# actuator_control_1_2_0.net
KiCad netlist of a schematic drawn in EAGLE
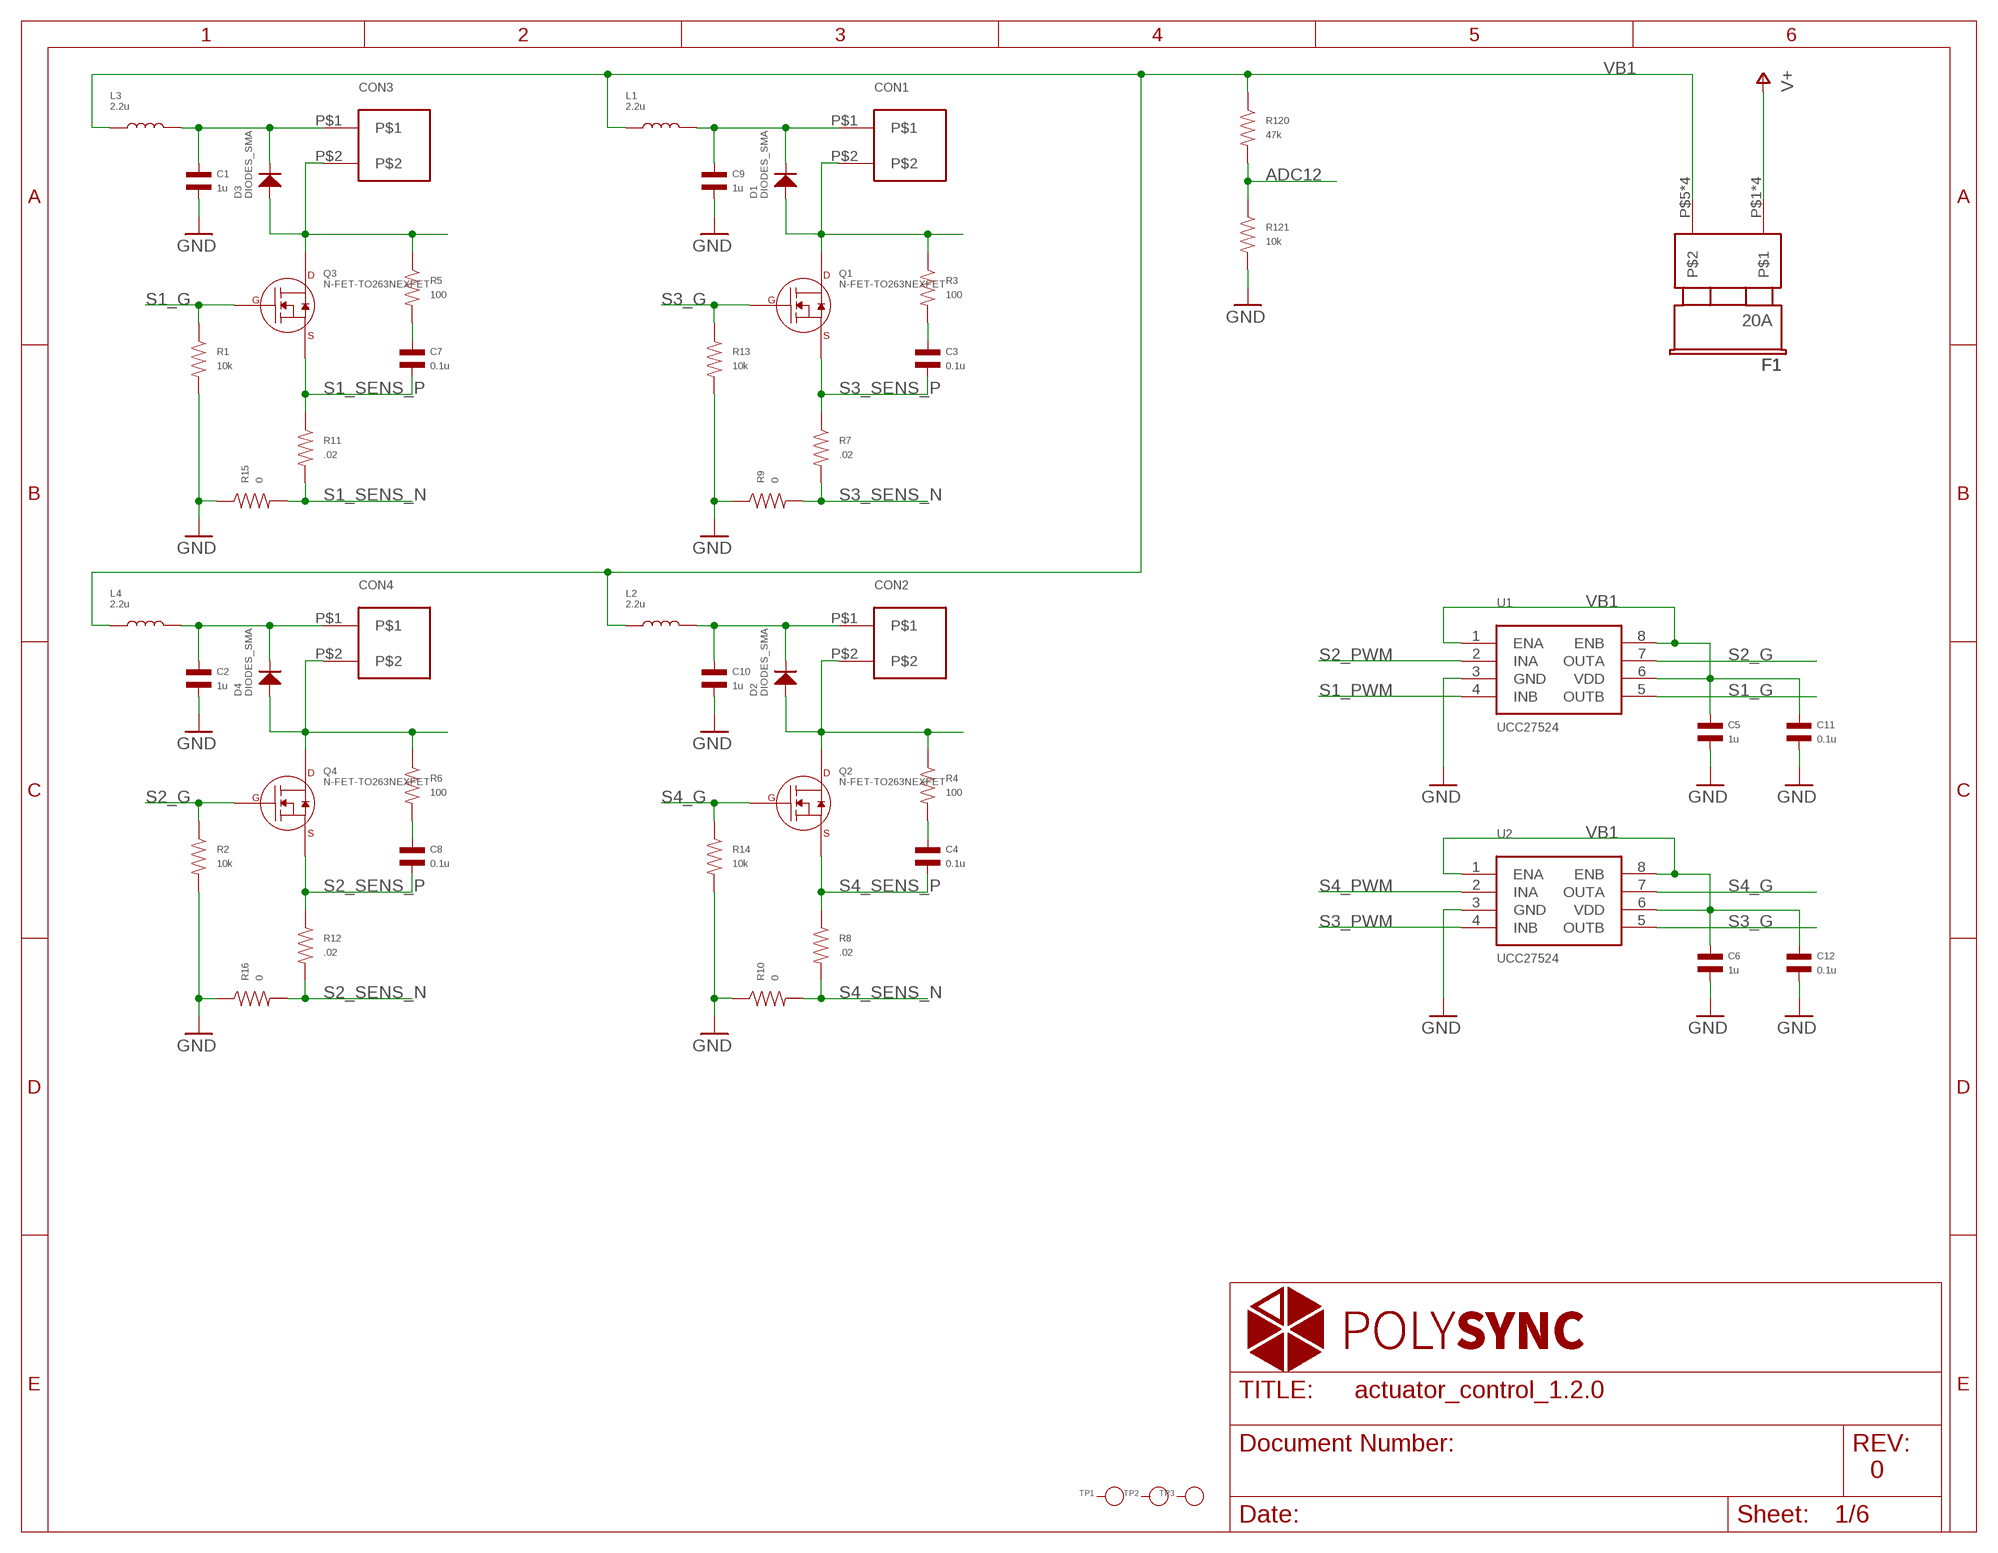
[diagram p0: schematic, sheet 1]
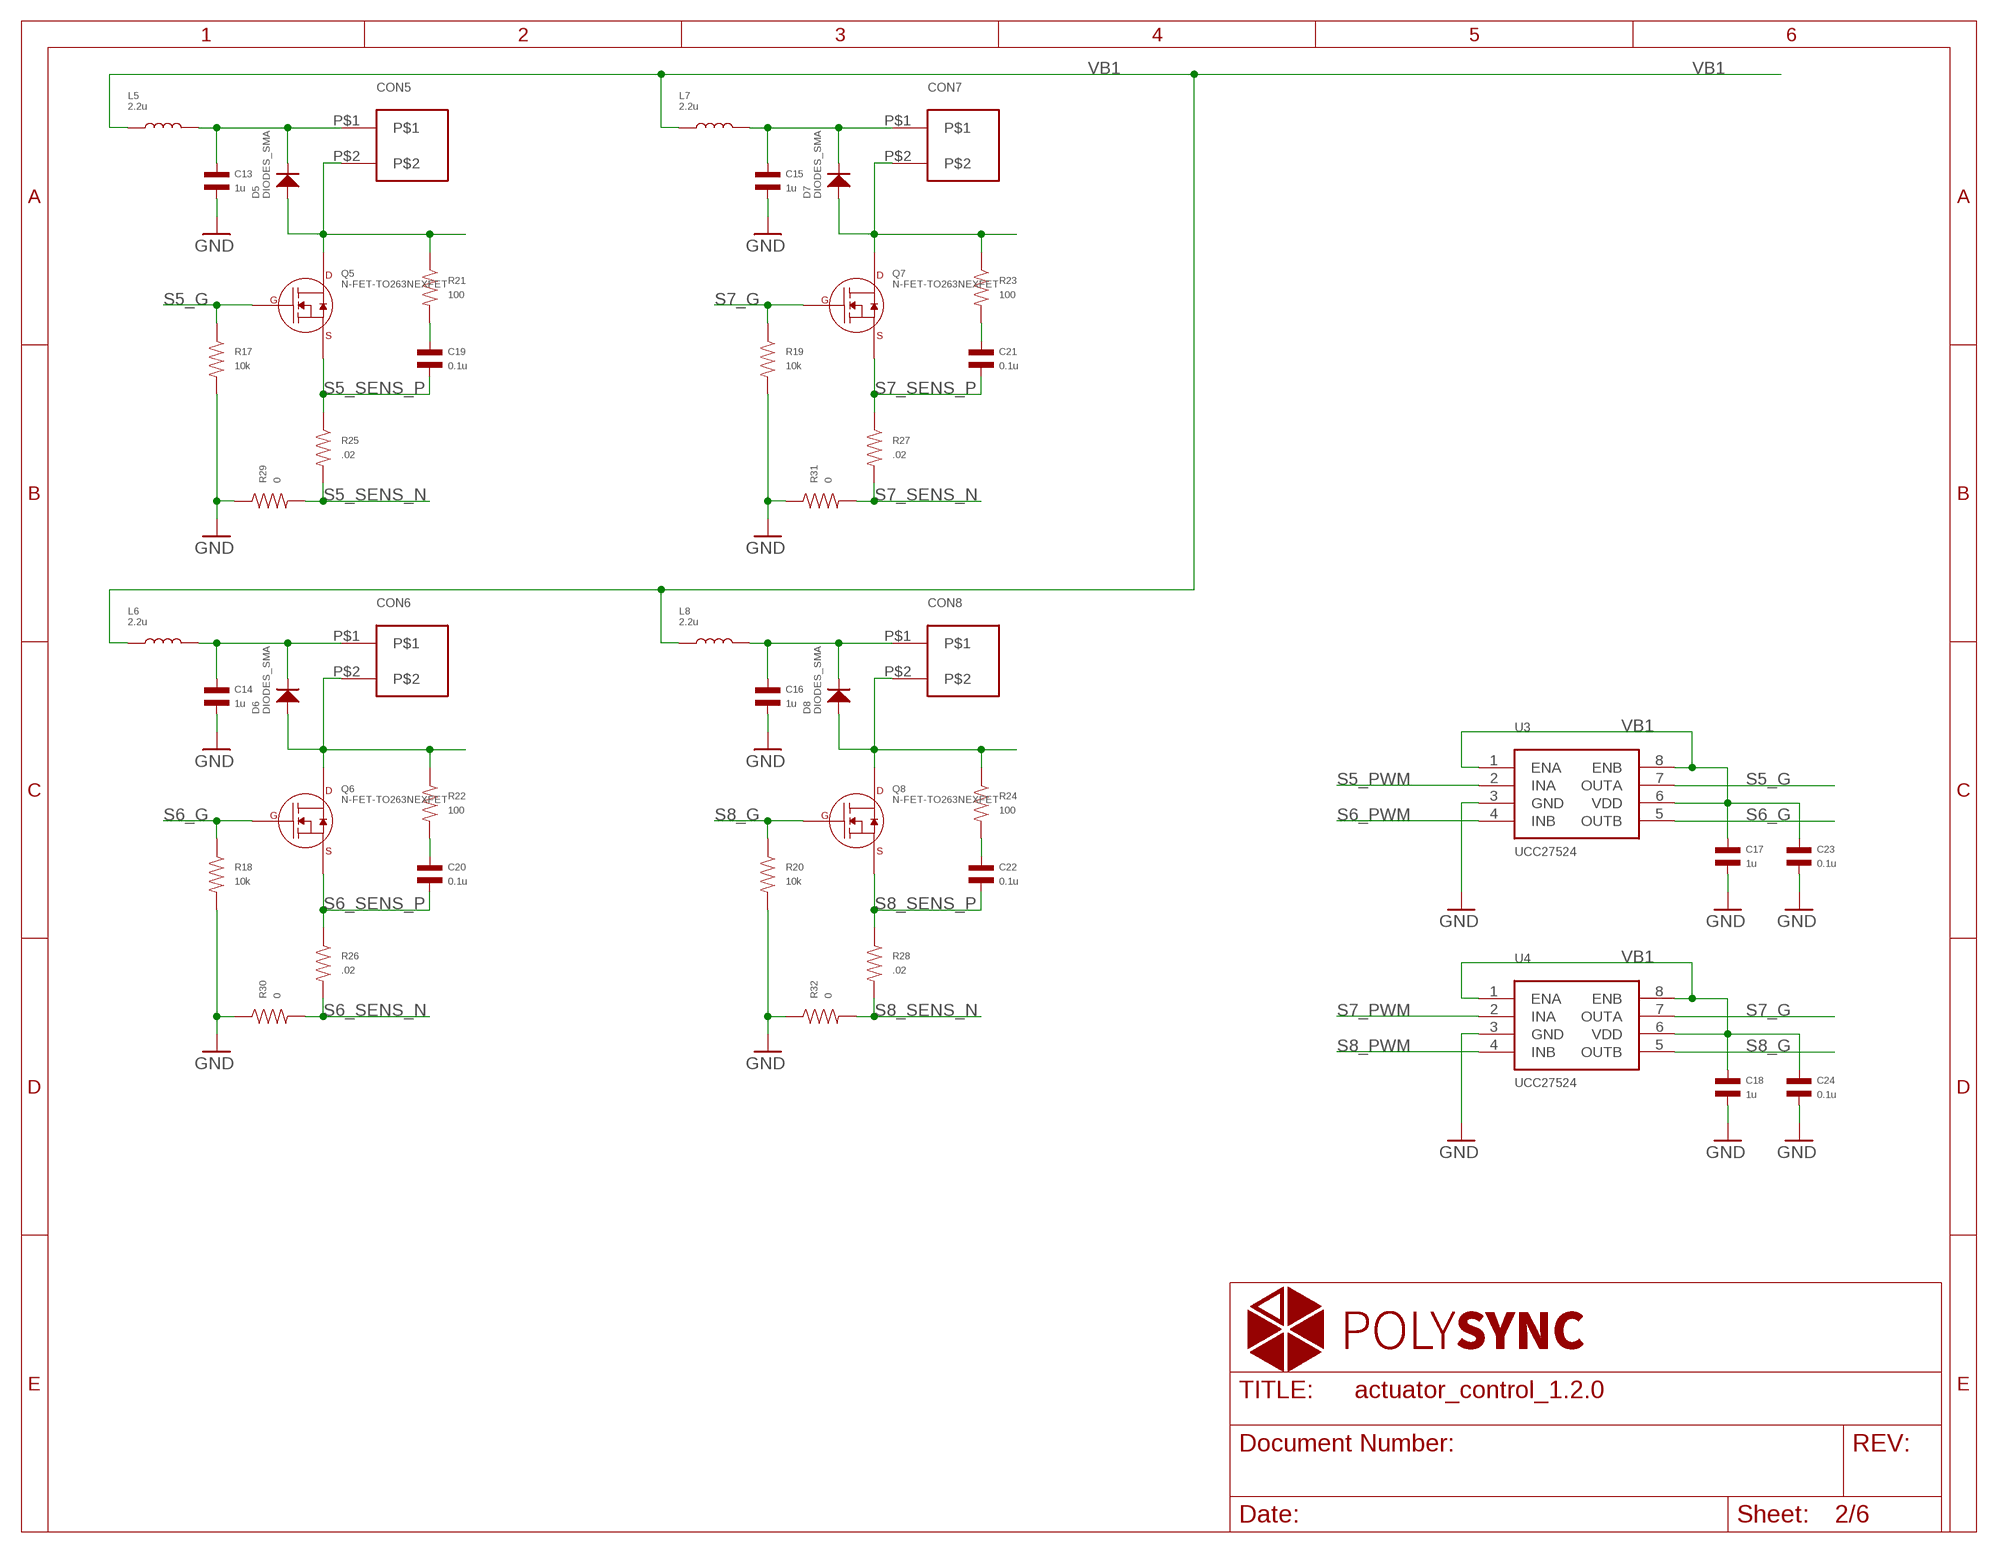
[diagram p1: schematic, sheet 2]
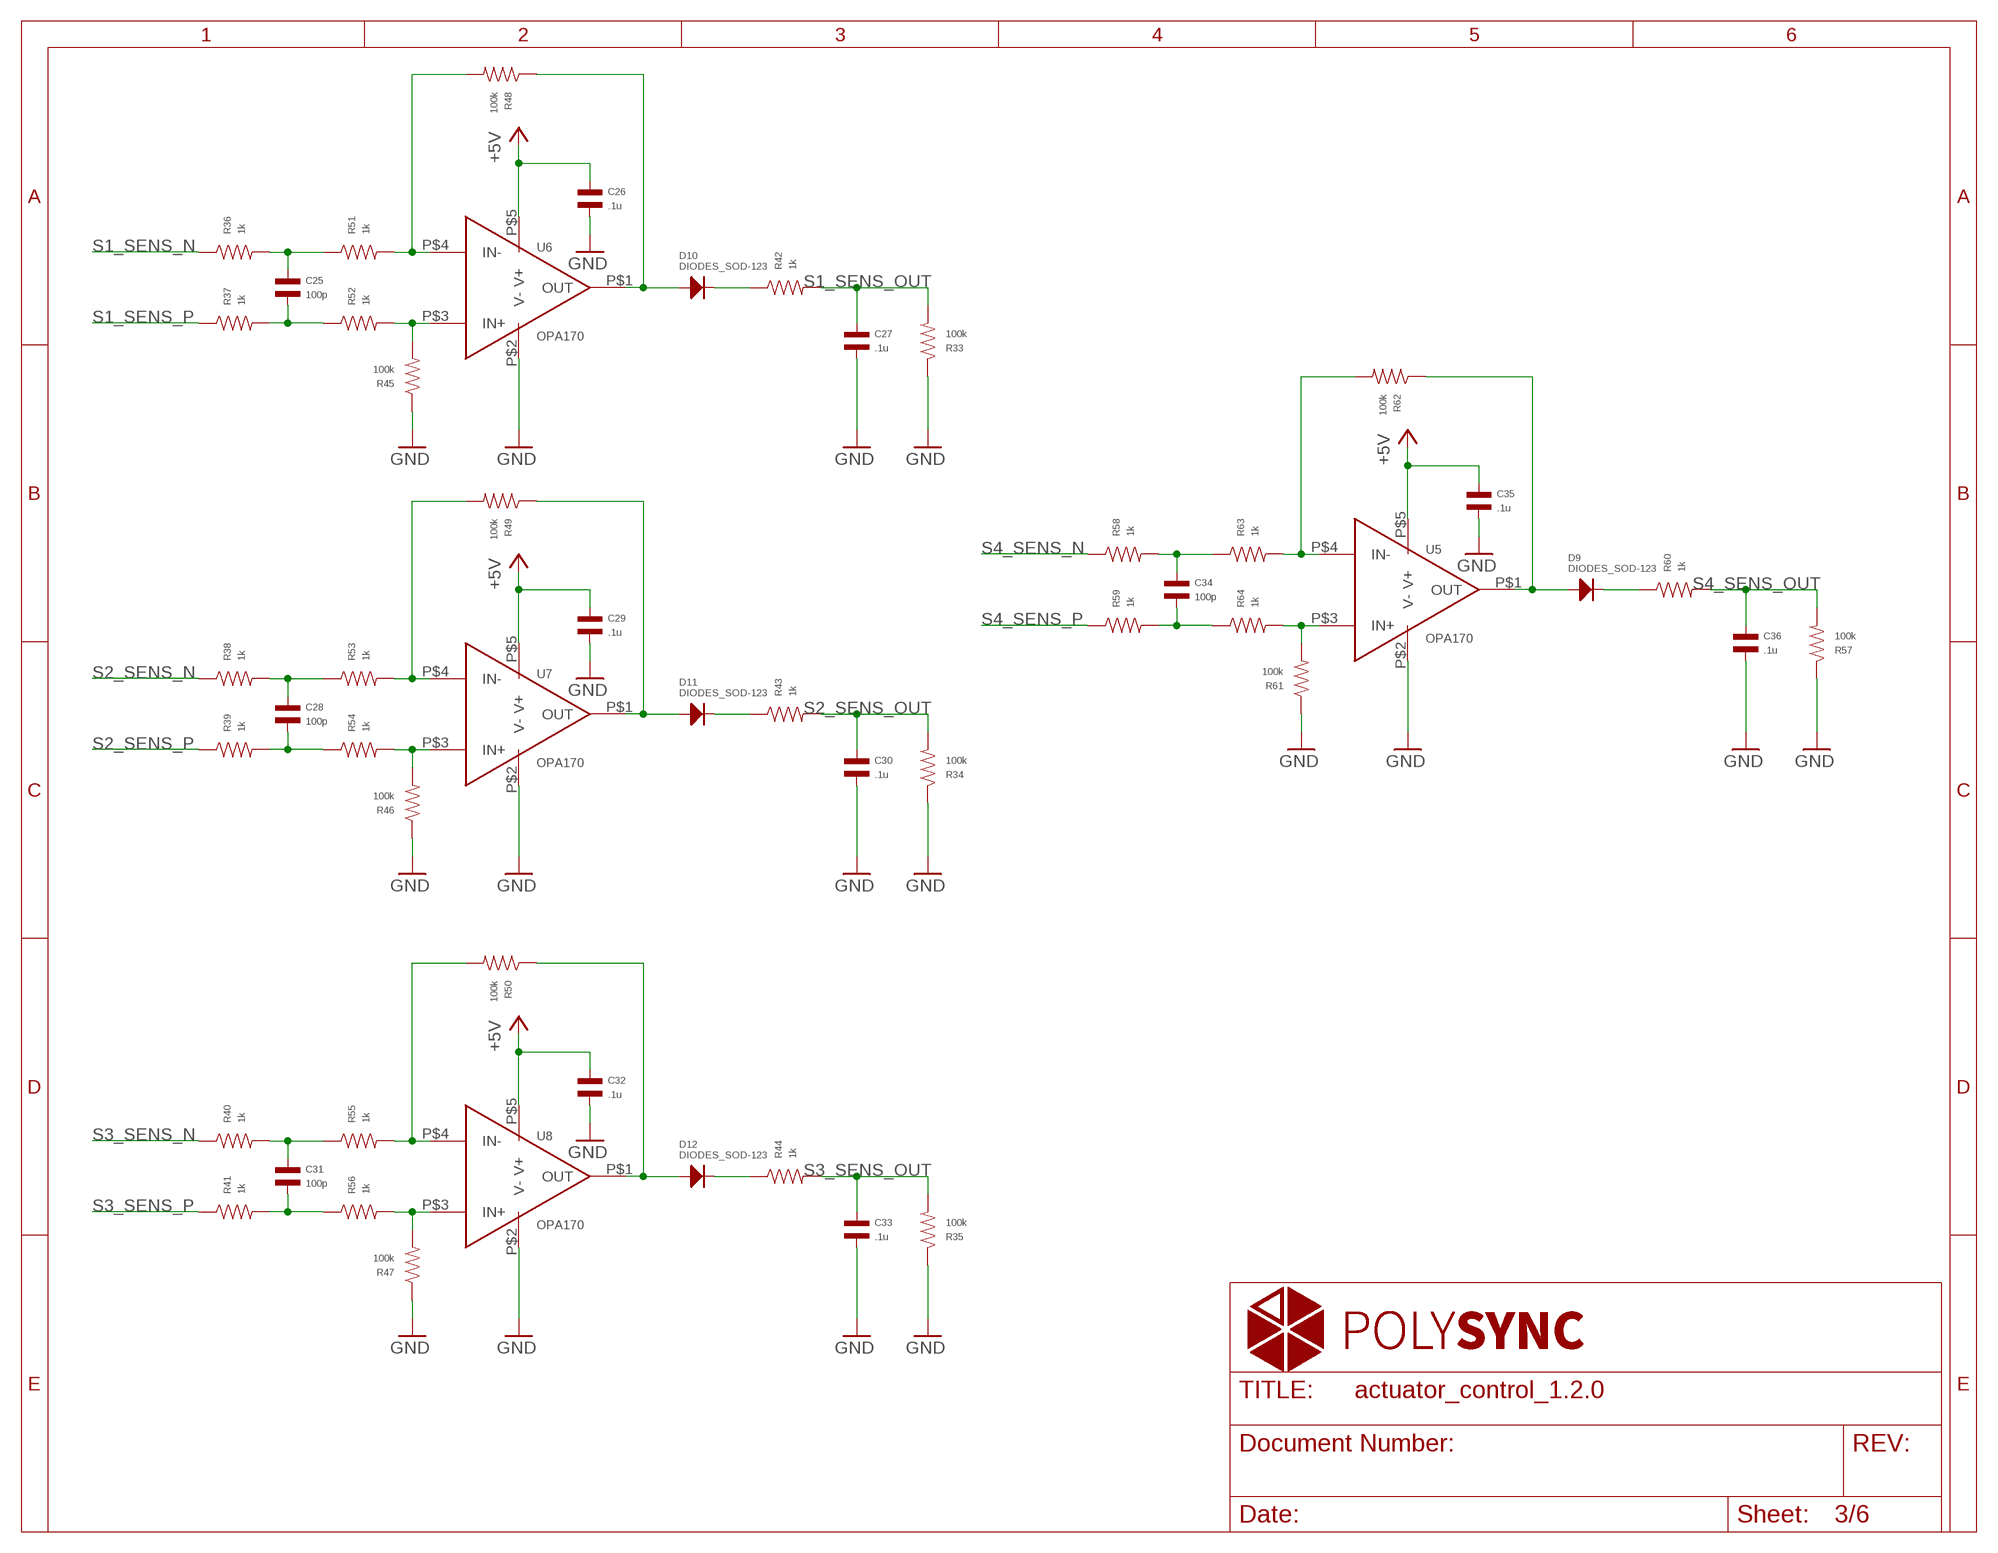
[diagram p2: schematic, sheet 3]
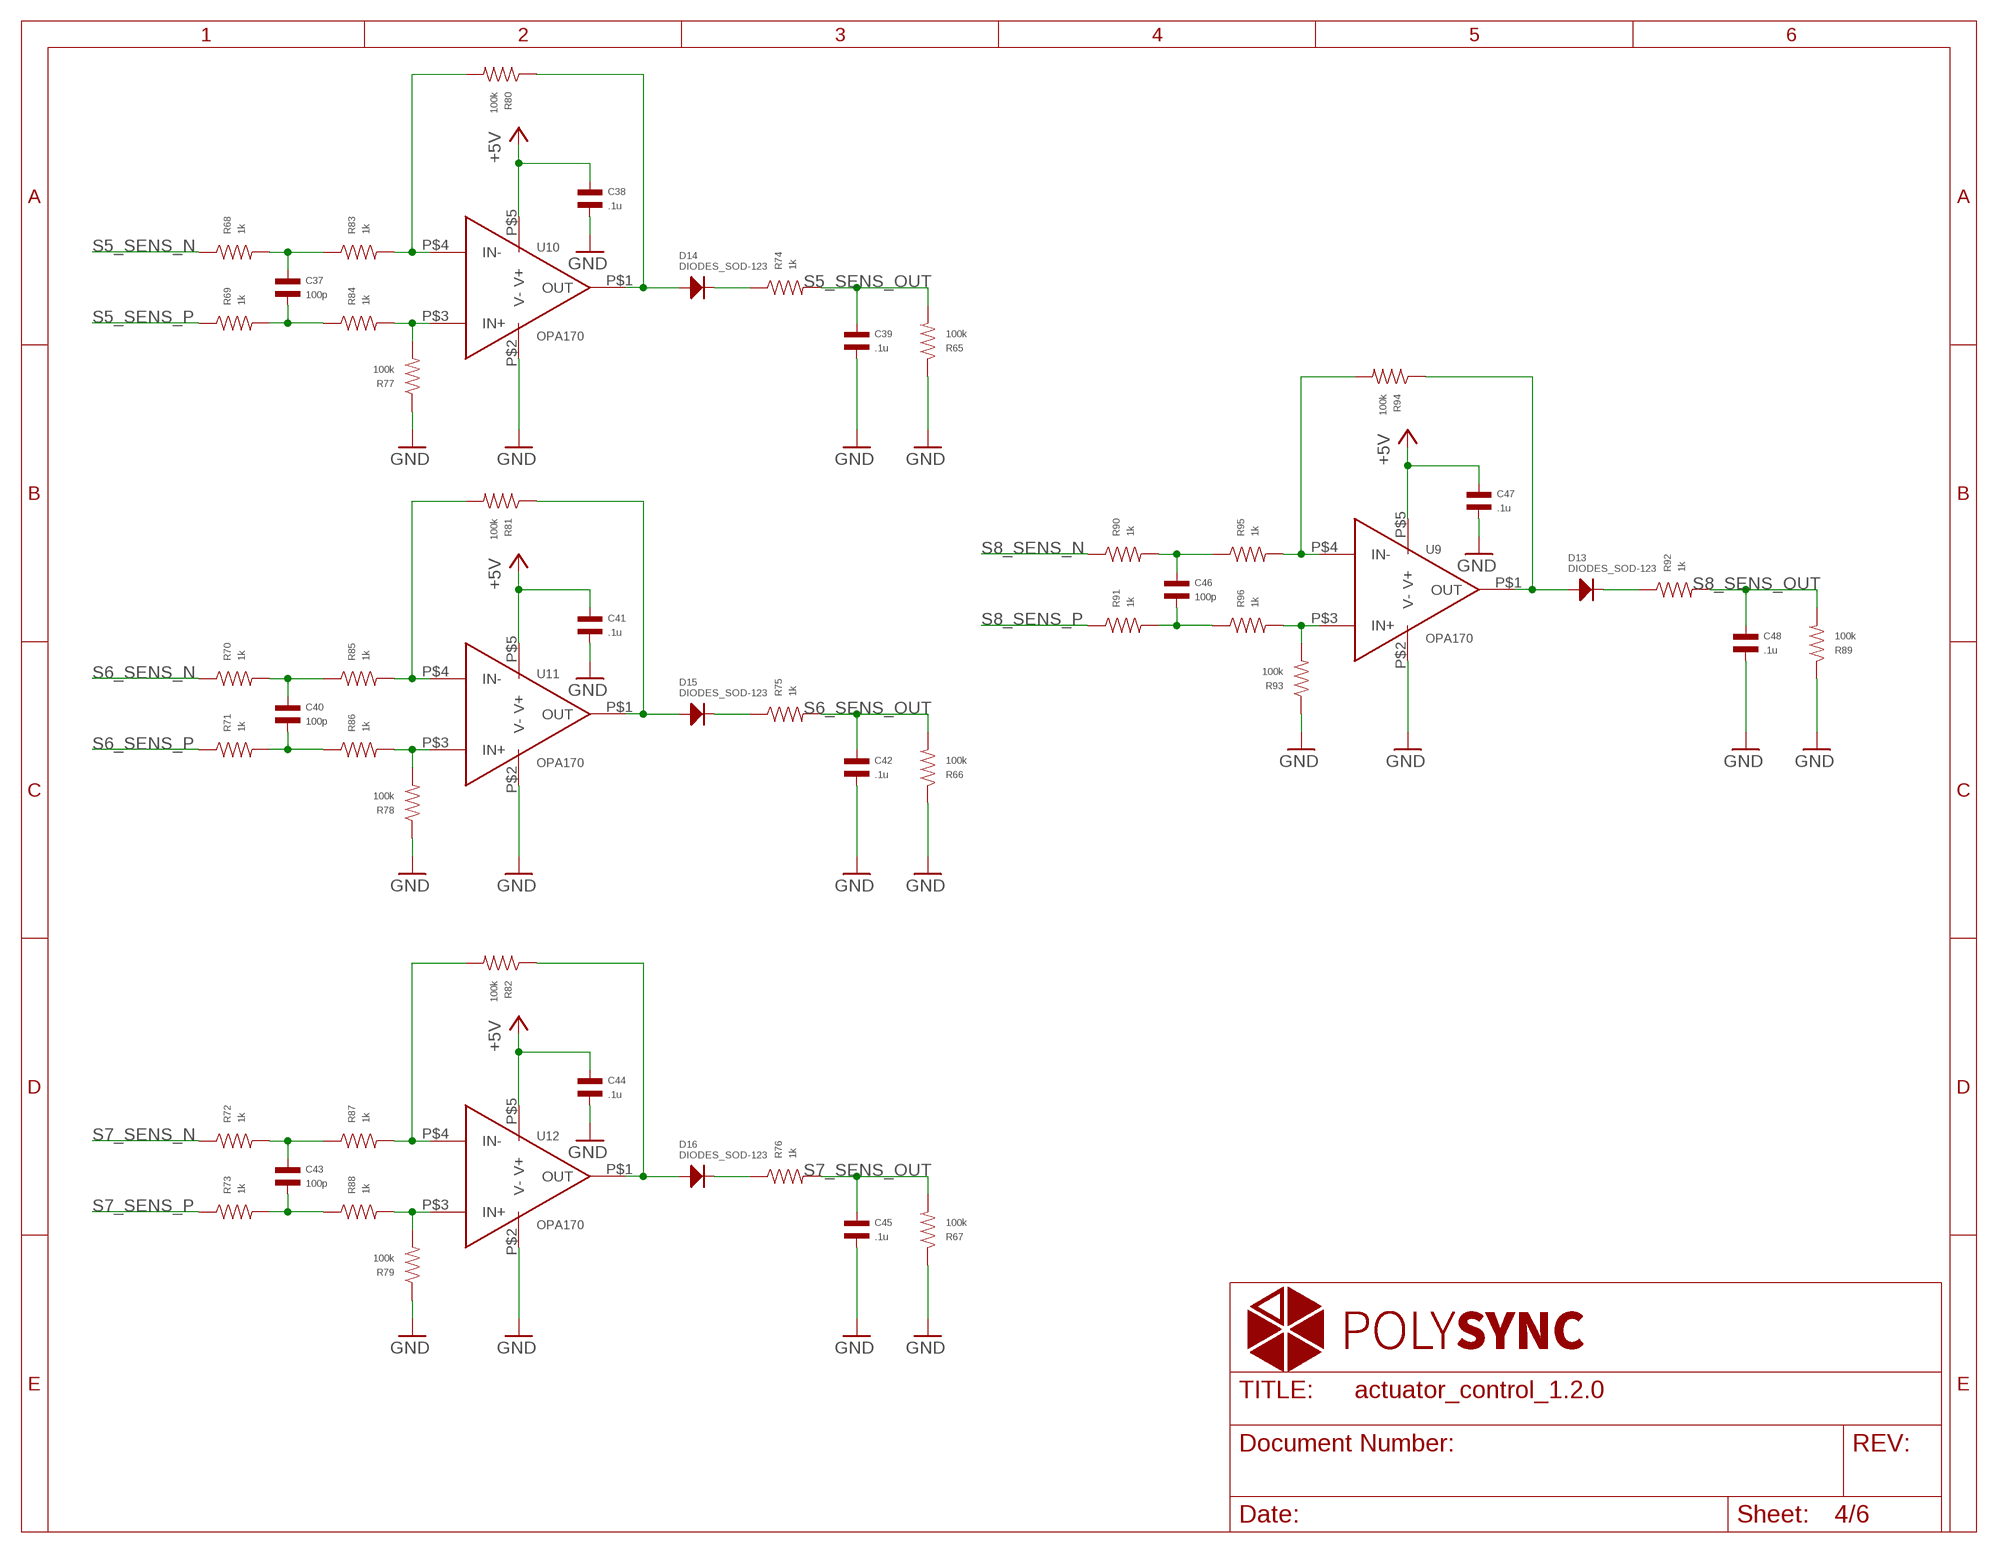
[diagram p3: schematic, sheet 4]
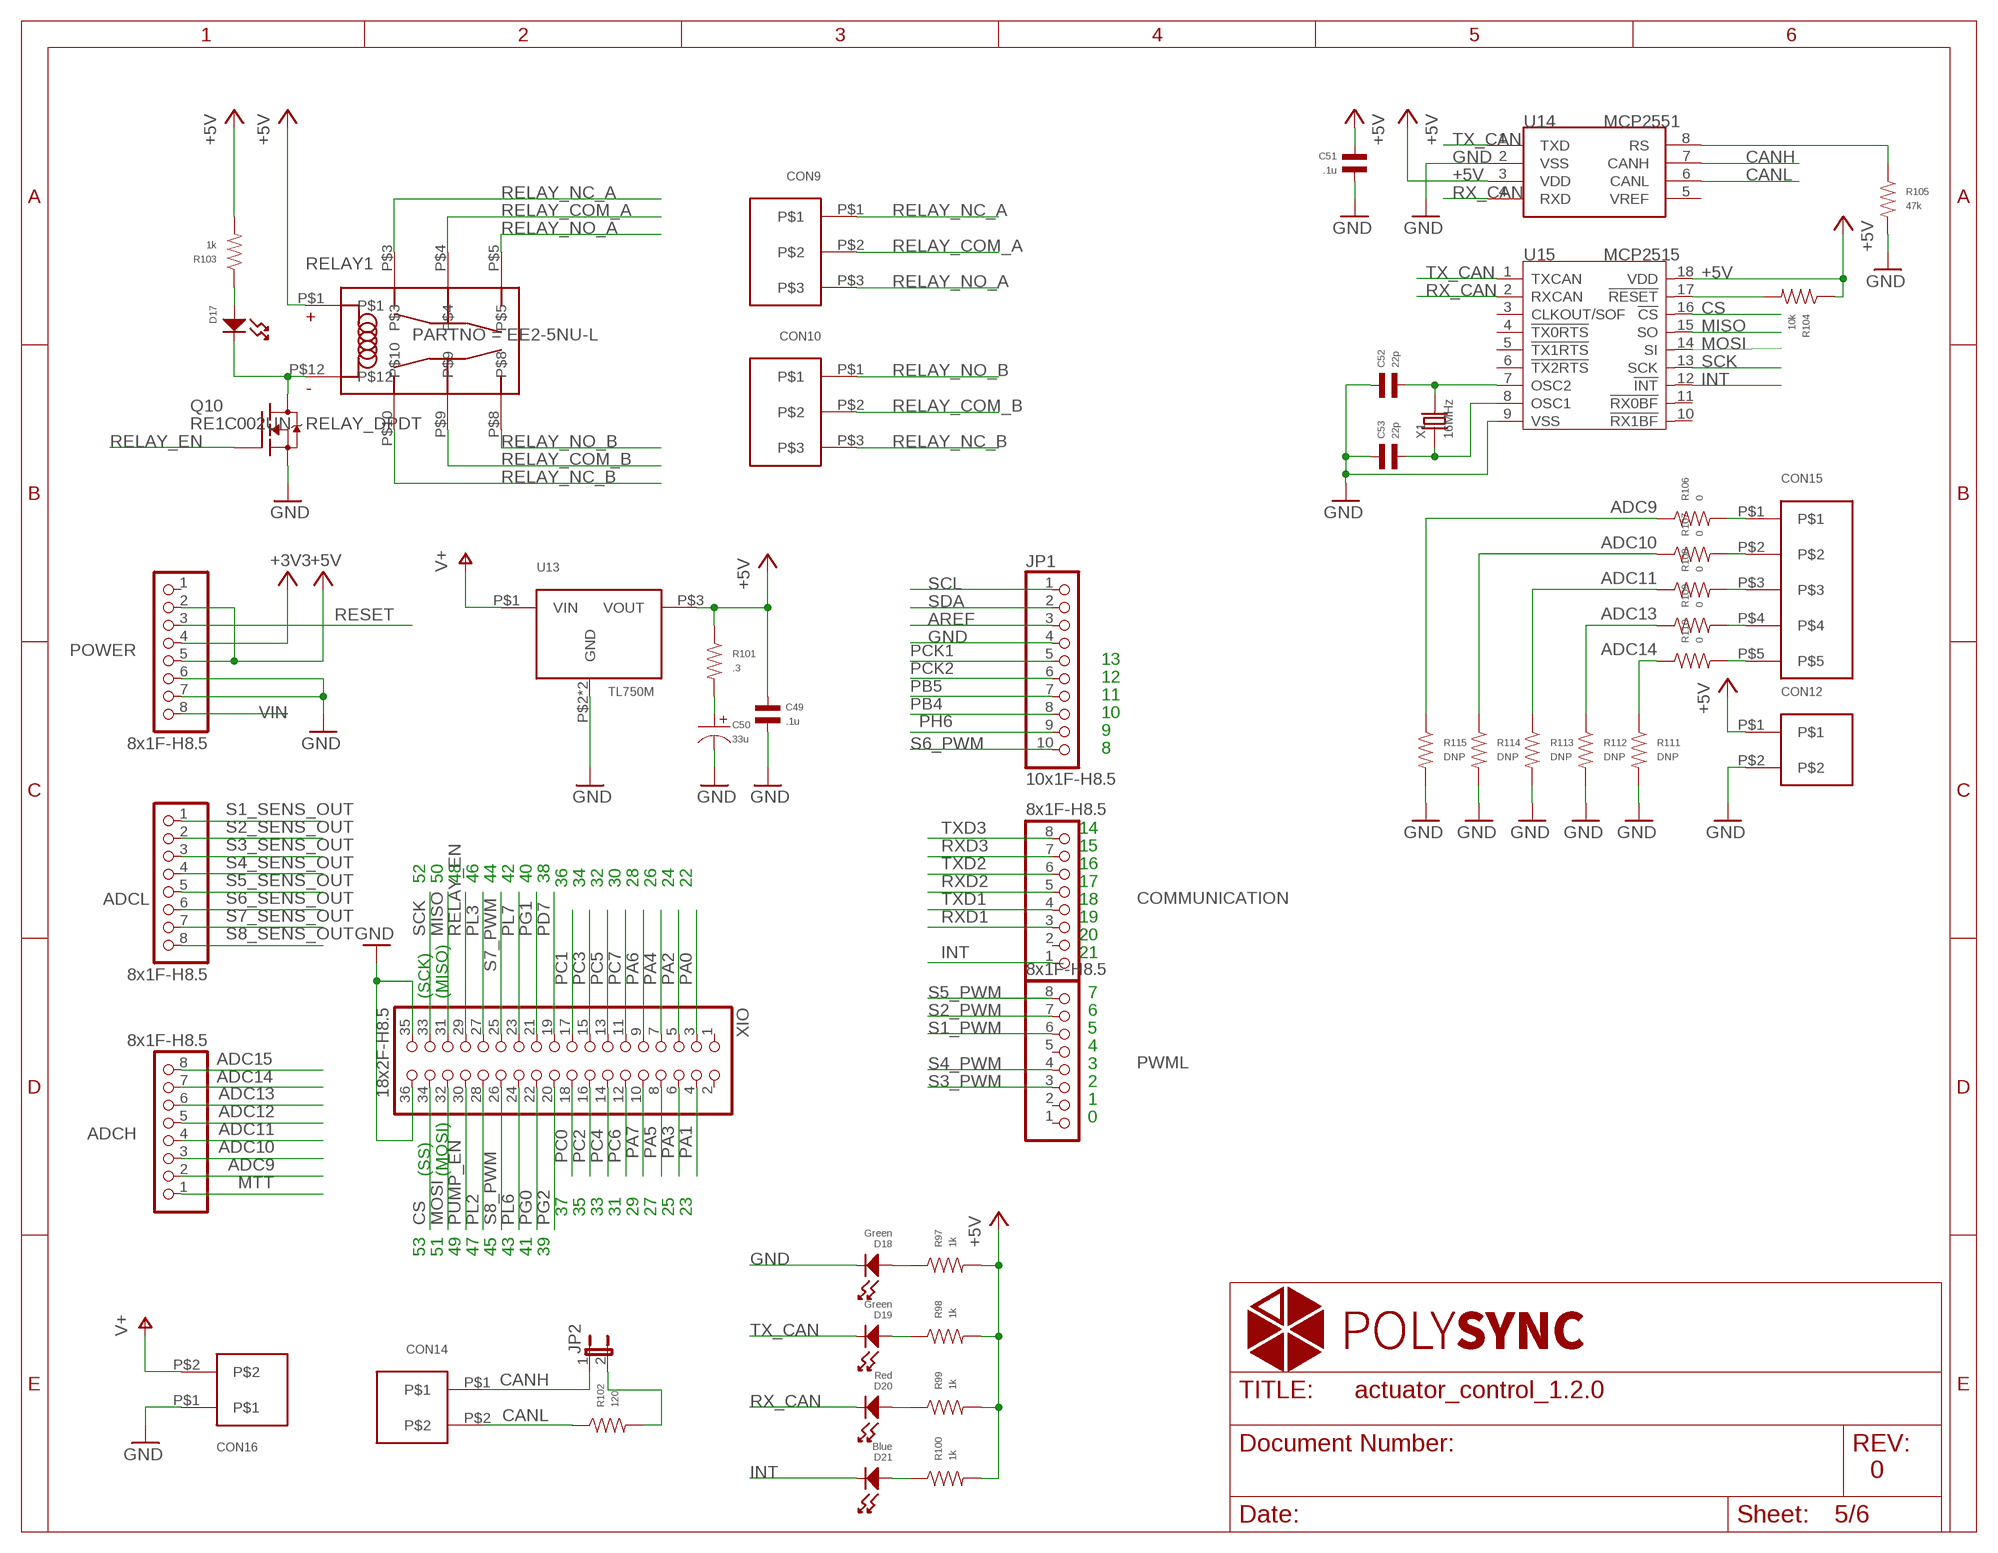
[diagram p4: schematic, sheet 5]
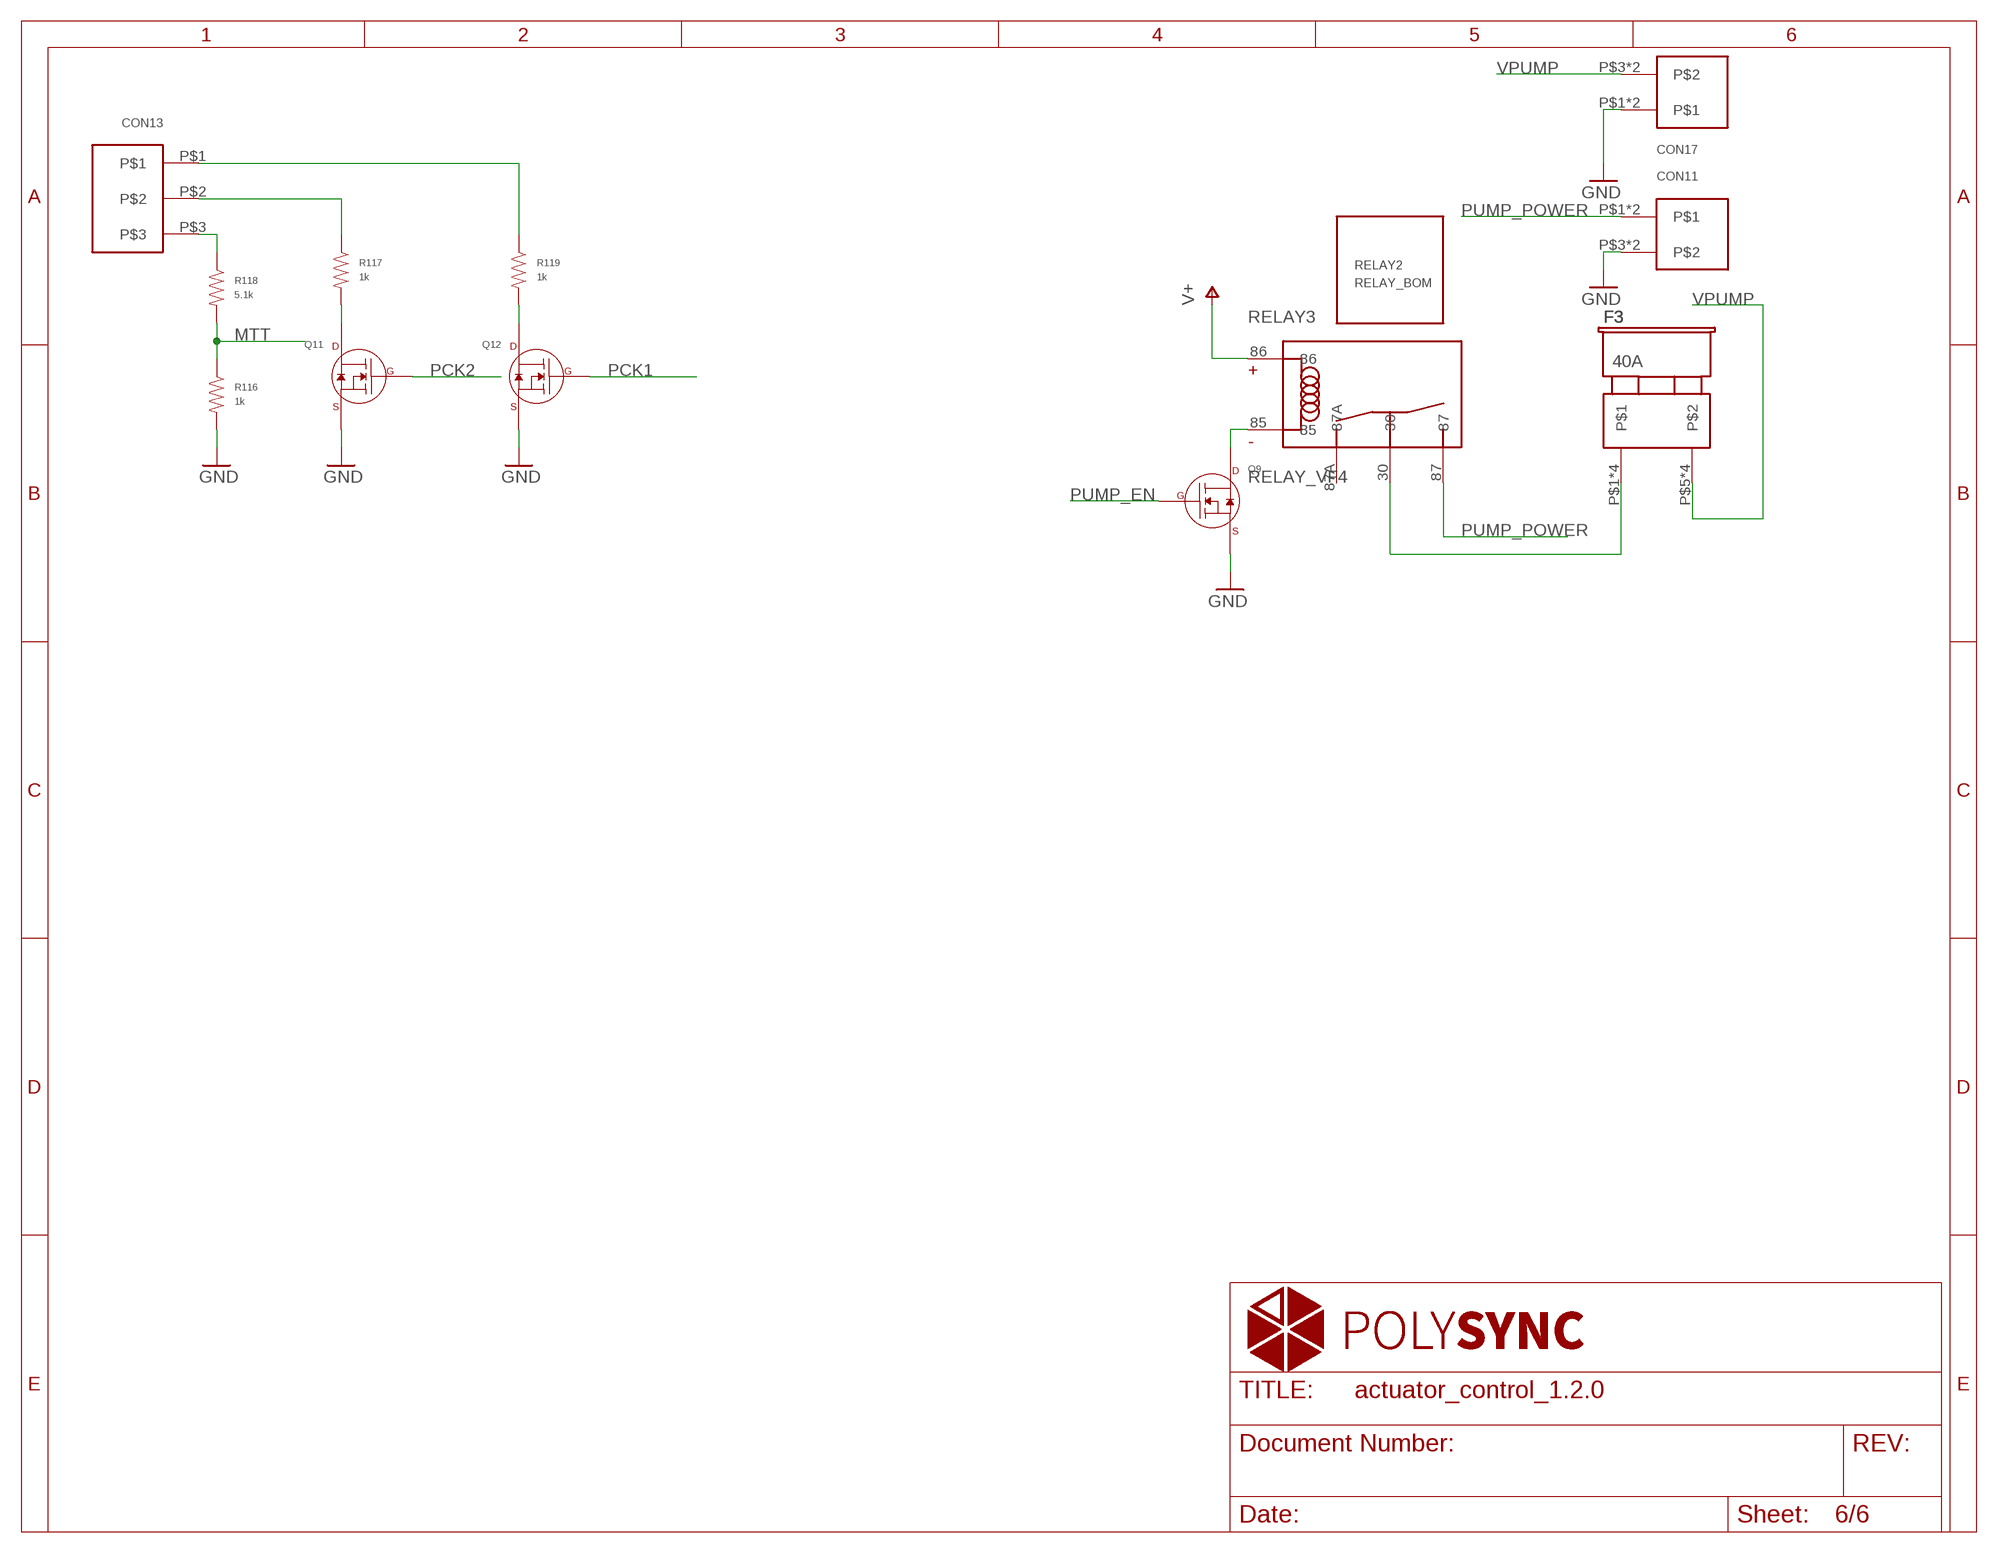
[diagram p5: schematic, sheet 6]

(export (version "E")
  (design (tool "Eeschema 10.0.6"))
  (components
    (comp (ref "C13")
      (value "1u")
      (footprint "eagle-import:C1206")
      (libsource (lib "eagle-import") (part "CAPACITOR_NP_1206"))
    )
    (comp (ref "C14")
      (value "1u")
      (footprint "eagle-import:C1206")
      (libsource (lib "eagle-import") (part "CAPACITOR_NP_1206"))
    )
    (comp (ref "C15")
      (value "1u")
      (footprint "eagle-import:C1206")
      (libsource (lib "eagle-import") (part "CAPACITOR_NP_1206"))
    )
    (comp (ref "C16")
      (value "1u")
      (footprint "eagle-import:C1206")
      (libsource (lib "eagle-import") (part "CAPACITOR_NP_1206"))
    )
    (comp (ref "C17")
      (value "1u")
      (footprint "eagle-import:C1206")
      (libsource (lib "eagle-import") (part "CAPACITOR_NP_1206"))
    )
    (comp (ref "C18")
      (value "1u")
      (footprint "eagle-import:C1206")
      (libsource (lib "eagle-import") (part "CAPACITOR_NP_1206"))
    )
    (comp (ref "C19")
      (value "0.1u")
      (footprint "eagle-import:C0805")
      (libsource (lib "eagle-import") (part "CAPACITOR_NP_0805"))
    )
    (comp (ref "C20")
      (value "0.1u")
      (footprint "eagle-import:C0805")
      (libsource (lib "eagle-import") (part "CAPACITOR_NP_0805"))
    )
    (comp (ref "C21")
      (value "0.1u")
      (footprint "eagle-import:C0805")
      (libsource (lib "eagle-import") (part "CAPACITOR_NP_0805"))
    )
    (comp (ref "C22")
      (value "0.1u")
      (footprint "eagle-import:C0805")
      (libsource (lib "eagle-import") (part "CAPACITOR_NP_0805"))
    )
    (comp (ref "C23")
      (value "0.1u")
      (footprint "eagle-import:C0805")
      (libsource (lib "eagle-import") (part "CAPACITOR_NP_0805"))
    )
    (comp (ref "C24")
      (value "0.1u")
      (footprint "eagle-import:C0805")
      (libsource (lib "eagle-import") (part "CAPACITOR_NP_0805"))
    )
    (comp (ref "CON5")
      (value "CON23.5MM")
      (footprint "eagle-import:PHOENIX_2_45")
      (libsource (lib "eagle-import") (part "CON23.5MM"))
    )
    (comp (ref "CON6")
      (value "CON23.5MM")
      (footprint "eagle-import:PHOENIX_2_45")
      (libsource (lib "eagle-import") (part "CON23.5MM"))
    )
    (comp (ref "CON7")
      (value "CON23.5MM")
      (footprint "eagle-import:PHOENIX_2_45")
      (libsource (lib "eagle-import") (part "CON23.5MM"))
    )
    (comp (ref "CON8")
      (value "CON23.5MM")
      (footprint "eagle-import:PHOENIX_2_45")
      (libsource (lib "eagle-import") (part "CON23.5MM"))
    )
    (comp (ref "D5")
      (value "DIODES_SMA")
      (footprint "eagle-import:SMA")
      (fields (field (name "HOUSEPART") "NO"))
      (libsource (lib "eagle-import") (part "DIODES_SMA"))
    )
    (comp (ref "D6")
      (value "DIODES_SMA")
      (footprint "eagle-import:SMA")
      (fields (field (name "HOUSEPART") "NO"))
      (libsource (lib "eagle-import") (part "DIODES_SMA"))
    )
    (comp (ref "D7")
      (value "DIODES_SMA")
      (footprint "eagle-import:SMA")
      (fields (field (name "HOUSEPART") "NO"))
      (libsource (lib "eagle-import") (part "DIODES_SMA"))
    )
    (comp (ref "D8")
      (value "DIODES_SMA")
      (footprint "eagle-import:SMA")
      (fields (field (name "HOUSEPART") "NO"))
      (libsource (lib "eagle-import") (part "DIODES_SMA"))
    )
    (comp (ref "L5")
      (value "2.2u")
      (footprint "eagle-import:SRP7050")
      (fields (field (name "MFG") "Bourns") (field (name "PARTNO") "SRP7050TA-2R2M"))
      (libsource (lib "eagle-import") (part "INDUCTORSRP7050"))
    )
    (comp (ref "L6")
      (value "2.2u")
      (footprint "eagle-import:SRP7050")
      (fields (field (name "MFG") "Bourns") (field (name "PARTNO") "SRP7050TA-2R2M"))
      (libsource (lib "eagle-import") (part "INDUCTORSRP7050"))
    )
    (comp (ref "L7")
      (value "2.2u")
      (footprint "eagle-import:SRP7050")
      (fields (field (name "MFG") "Bourns") (field (name "PARTNO") "SRP7050TA-2R2M"))
      (libsource (lib "eagle-import") (part "INDUCTORSRP7050"))
    )
    (comp (ref "L8")
      (value "2.2u")
      (footprint "eagle-import:SRP7050")
      (fields (field (name "MFG") "Bourns") (field (name "PARTNO") "SRP7050TA-2R2M"))
      (libsource (lib "eagle-import") (part "INDUCTORSRP7050"))
    )
    (comp (ref "Q5")
      (value "N-FET-TO263NEXFET")
      (footprint "eagle-import:SON8-DQJ")
      (libsource (lib "eagle-import") (part "N-FET-TO263NEXFET"))
    )
    (comp (ref "Q6")
      (value "N-FET-TO263NEXFET")
      (footprint "eagle-import:SON8-DQJ")
      (libsource (lib "eagle-import") (part "N-FET-TO263NEXFET"))
    )
    (comp (ref "Q7")
      (value "N-FET-TO263NEXFET")
      (footprint "eagle-import:SON8-DQJ")
      (libsource (lib "eagle-import") (part "N-FET-TO263NEXFET"))
    )
    (comp (ref "Q8")
      (value "N-FET-TO263NEXFET")
      (footprint "eagle-import:SON8-DQJ")
      (libsource (lib "eagle-import") (part "N-FET-TO263NEXFET"))
    )
    (comp (ref "R17")
      (value "10k")
      (footprint "eagle-import:R0402")
      (libsource (lib "eagle-import") (part "RESISTOR_0402"))
    )
    (comp (ref "R18")
      (value "10k")
      (footprint "eagle-import:R0402")
      (libsource (lib "eagle-import") (part "RESISTOR_0402"))
    )
    (comp (ref "R19")
      (value "10k")
      (footprint "eagle-import:R0402")
      (libsource (lib "eagle-import") (part "RESISTOR_0402"))
    )
    (comp (ref "R20")
      (value "10k")
      (footprint "eagle-import:R0402")
      (libsource (lib "eagle-import") (part "RESISTOR_0402"))
    )
    (comp (ref "R21")
      (value "100")
      (footprint "eagle-import:R0805")
      (libsource (lib "eagle-import") (part "RESISTOR_0805"))
    )
    (comp (ref "R22")
      (value "100")
      (footprint "eagle-import:R0805")
      (libsource (lib "eagle-import") (part "RESISTOR_0805"))
    )
    (comp (ref "R23")
      (value "100")
      (footprint "eagle-import:R0805")
      (libsource (lib "eagle-import") (part "RESISTOR_0805"))
    )
    (comp (ref "R24")
      (value "100")
      (footprint "eagle-import:R0805")
      (libsource (lib "eagle-import") (part "RESISTOR_0805"))
    )
    (comp (ref "R25")
      (value ".02")
      (footprint "eagle-import:R1206")
      (libsource (lib "eagle-import") (part "RESISTOR_1206"))
    )
    (comp (ref "R26")
      (value ".02")
      (footprint "eagle-import:R1206")
      (libsource (lib "eagle-import") (part "RESISTOR_1206"))
    )
    (comp (ref "R27")
      (value ".02")
      (footprint "eagle-import:R1206")
      (libsource (lib "eagle-import") (part "RESISTOR_1206"))
    )
    (comp (ref "R28")
      (value ".02")
      (footprint "eagle-import:R1206")
      (libsource (lib "eagle-import") (part "RESISTOR_1206"))
    )
    (comp (ref "R29")
      (value "0")
      (footprint "eagle-import:R0805")
      (libsource (lib "eagle-import") (part "RESISTOR_0805"))
    )
    (comp (ref "R30")
      (value "0")
      (footprint "eagle-import:R0805")
      (libsource (lib "eagle-import") (part "RESISTOR_0805"))
    )
    (comp (ref "R31")
      (value "0")
      (footprint "eagle-import:R0805")
      (libsource (lib "eagle-import") (part "RESISTOR_0805"))
    )
    (comp (ref "R32")
      (value "0")
      (footprint "eagle-import:R0805")
      (libsource (lib "eagle-import") (part "RESISTOR_0805"))
    )
    (comp (ref "U3")
      (value "UCC27524")
      (footprint "eagle-import:SOIC-8")
      (libsource (lib "eagle-import") (part "UCC27524"))
    )
    (comp (ref "U4")
      (value "UCC27524")
      (footprint "eagle-import:SOIC-8")
      (libsource (lib "eagle-import") (part "UCC27524"))
    )
    (comp (ref "C1")
      (value "1u")
      (footprint "eagle-import:C1206")
      (libsource (lib "eagle-import") (part "CAPACITOR_NP_1206"))
    )
    (comp (ref "C2")
      (value "1u")
      (footprint "eagle-import:C1206")
      (libsource (lib "eagle-import") (part "CAPACITOR_NP_1206"))
    )
    (comp (ref "C3")
      (value "0.1u")
      (footprint "eagle-import:C0805")
      (libsource (lib "eagle-import") (part "CAPACITOR_NP_0805"))
    )
    (comp (ref "C4")
      (value "0.1u")
      (footprint "eagle-import:C0805")
      (libsource (lib "eagle-import") (part "CAPACITOR_NP_0805"))
    )
    (comp (ref "C5")
      (value "1u")
      (footprint "eagle-import:C1206")
      (libsource (lib "eagle-import") (part "CAPACITOR_NP_1206"))
    )
    (comp (ref "C6")
      (value "1u")
      (footprint "eagle-import:C1206")
      (libsource (lib "eagle-import") (part "CAPACITOR_NP_1206"))
    )
    (comp (ref "C7")
      (value "0.1u")
      (footprint "eagle-import:C0805")
      (libsource (lib "eagle-import") (part "CAPACITOR_NP_0805"))
    )
    (comp (ref "C8")
      (value "0.1u")
      (footprint "eagle-import:C0805")
      (libsource (lib "eagle-import") (part "CAPACITOR_NP_0805"))
    )
    (comp (ref "C9")
      (value "1u")
      (footprint "eagle-import:C1206")
      (libsource (lib "eagle-import") (part "CAPACITOR_NP_1206"))
    )
    (comp (ref "C10")
      (value "1u")
      (footprint "eagle-import:C1206")
      (libsource (lib "eagle-import") (part "CAPACITOR_NP_1206"))
    )
    (comp (ref "C11")
      (value "0.1u")
      (footprint "eagle-import:C0805")
      (libsource (lib "eagle-import") (part "CAPACITOR_NP_0805"))
    )
    (comp (ref "C12")
      (value "0.1u")
      (footprint "eagle-import:C0805")
      (libsource (lib "eagle-import") (part "CAPACITOR_NP_0805"))
    )
    (comp (ref "CON1")
      (value "CON23.5MM")
      (footprint "eagle-import:PHOENIX_2_45")
      (libsource (lib "eagle-import") (part "CON23.5MM"))
    )
    (comp (ref "CON2")
      (value "CON23.5MM")
      (footprint "eagle-import:PHOENIX_2_45")
      (libsource (lib "eagle-import") (part "CON23.5MM"))
    )
    (comp (ref "CON3")
      (value "CON23.5MM")
      (footprint "eagle-import:PHOENIX_2_45")
      (libsource (lib "eagle-import") (part "CON23.5MM"))
    )
    (comp (ref "CON4")
      (value "CON23.5MM")
      (footprint "eagle-import:PHOENIX_2_45")
      (libsource (lib "eagle-import") (part "CON23.5MM"))
    )
    (comp (ref "D1")
      (value "DIODES_SMA")
      (footprint "eagle-import:SMA")
      (fields (field (name "HOUSEPART") "NO"))
      (libsource (lib "eagle-import") (part "DIODES_SMA"))
    )
    (comp (ref "D2")
      (value "DIODES_SMA")
      (footprint "eagle-import:SMA")
      (fields (field (name "HOUSEPART") "NO"))
      (libsource (lib "eagle-import") (part "DIODES_SMA"))
    )
    (comp (ref "D3")
      (value "DIODES_SMA")
      (footprint "eagle-import:SMA")
      (fields
        (field (name "HOUSEPART") "NO")
        (field (name "MFG") "Diodes Inc")
        (field (name "MPN") "US1B-13-F")
      )
      (libsource (lib "eagle-import") (part "DIODES_SMA"))
    )
    (comp (ref "D4")
      (value "DIODES_SMA")
      (footprint "eagle-import:SMA")
      (fields (field (name "HOUSEPART") "NO"))
      (libsource (lib "eagle-import") (part "DIODES_SMA"))
    )
    (comp (ref "F1")
      (value "20A")
      (footprint "eagle-import:FUSE_ATO")
      (fields (field (name "MFG") "Littelfuse") (field (name "PARTNO") "178.6165.0001"))
      (libsource (lib "eagle-import") (part "FUSE"))
    )
    (comp (ref "L1")
      (value "2.2u")
      (footprint "eagle-import:SRP7050")
      (fields (field (name "MFG") "Bourns") (field (name "PARTNO") "SRP7050TA-2R2M"))
      (libsource (lib "eagle-import") (part "INDUCTORSRP7050"))
    )
    (comp (ref "L2")
      (value "2.2u")
      (footprint "eagle-import:SRP7050")
      (fields (field (name "MFG") "Bourns") (field (name "PARTNO") "SRP7050TA-2R2M"))
      (libsource (lib "eagle-import") (part "INDUCTORSRP7050"))
    )
    (comp (ref "L3")
      (value "2.2u")
      (footprint "eagle-import:SRP7050")
      (fields (field (name "MFG") "Bourns") (field (name "PARTNO") "SRP7050TA-2R2M"))
      (libsource (lib "eagle-import") (part "INDUCTORSRP7050"))
    )
    (comp (ref "L4")
      (value "2.2u")
      (footprint "eagle-import:SRP7050")
      (fields (field (name "MFG") "Bourns") (field (name "PARTNO") "SRP7050TA-2R2M"))
      (libsource (lib "eagle-import") (part "INDUCTORSRP7050"))
    )
    (comp (ref "Q1")
      (value "N-FET-TO263NEXFET")
      (footprint "eagle-import:SON8-DQJ")
      (libsource (lib "eagle-import") (part "N-FET-TO263NEXFET"))
    )
    (comp (ref "Q2")
      (value "N-FET-TO263NEXFET")
      (footprint "eagle-import:SON8-DQJ")
      (libsource (lib "eagle-import") (part "N-FET-TO263NEXFET"))
    )
    (comp (ref "Q3")
      (value "N-FET-TO263NEXFET")
      (footprint "eagle-import:SON8-DQJ")
      (libsource (lib "eagle-import") (part "N-FET-TO263NEXFET"))
    )
    (comp (ref "Q4")
      (value "N-FET-TO263NEXFET")
      (footprint "eagle-import:SON8-DQJ")
      (libsource (lib "eagle-import") (part "N-FET-TO263NEXFET"))
    )
    (comp (ref "R1")
      (value "10k")
      (footprint "eagle-import:R0402")
      (libsource (lib "eagle-import") (part "RESISTOR_0402"))
    )
    (comp (ref "R2")
      (value "10k")
      (footprint "eagle-import:R0402")
      (libsource (lib "eagle-import") (part "RESISTOR_0402"))
    )
    (comp (ref "R3")
      (value "100")
      (footprint "eagle-import:R0805")
      (libsource (lib "eagle-import") (part "RESISTOR_0805"))
    )
    (comp (ref "R4")
      (value "100")
      (footprint "eagle-import:R0805")
      (libsource (lib "eagle-import") (part "RESISTOR_0805"))
    )
    (comp (ref "R5")
      (value "100")
      (footprint "eagle-import:R0805")
      (libsource (lib "eagle-import") (part "RESISTOR_0805"))
    )
    (comp (ref "R6")
      (value "100")
      (footprint "eagle-import:R0805")
      (libsource (lib "eagle-import") (part "RESISTOR_0805"))
    )
    (comp (ref "R7")
      (value ".02")
      (footprint "eagle-import:R1206")
      (libsource (lib "eagle-import") (part "RESISTOR_1206"))
    )
    (comp (ref "R8")
      (value ".02")
      (footprint "eagle-import:R1206")
      (libsource (lib "eagle-import") (part "RESISTOR_1206"))
    )
    (comp (ref "R9")
      (value "0")
      (footprint "eagle-import:R0805")
      (libsource (lib "eagle-import") (part "RESISTOR_0805"))
    )
    (comp (ref "R10")
      (value "0")
      (footprint "eagle-import:R0805")
      (libsource (lib "eagle-import") (part "RESISTOR_0805"))
    )
    (comp (ref "R11")
      (value ".02")
      (footprint "eagle-import:R1206")
      (libsource (lib "eagle-import") (part "RESISTOR_1206"))
    )
    (comp (ref "R12")
      (value ".02")
      (footprint "eagle-import:R1206")
      (libsource (lib "eagle-import") (part "RESISTOR_1206"))
    )
    (comp (ref "R13")
      (value "10k")
      (footprint "eagle-import:R0402")
      (libsource (lib "eagle-import") (part "RESISTOR_0402"))
    )
    (comp (ref "R14")
      (value "10k")
      (footprint "eagle-import:R0402")
      (libsource (lib "eagle-import") (part "RESISTOR_0402"))
    )
    (comp (ref "R15")
      (value "0")
      (footprint "eagle-import:R0805")
      (libsource (lib "eagle-import") (part "RESISTOR_0805"))
    )
    (comp (ref "R16")
      (value "0")
      (footprint "eagle-import:R0805")
      (libsource (lib "eagle-import") (part "RESISTOR_0805"))
    )
    (comp (ref "R120")
      (value "47k")
      (footprint "eagle-import:R0402")
      (libsource (lib "eagle-import") (part "RESISTOR_0402"))
    )
    (comp (ref "R121")
      (value "10k")
      (footprint "eagle-import:R0402")
      (libsource (lib "eagle-import") (part "RESISTOR_0402"))
    )
    (comp (ref "TP1")
      (value "PAD-TEST-POINT'4545'")
      (footprint "eagle-import:TP_4545")
      (fields (field (name "PARTNO") "DNP"))
      (libsource (lib "eagle-import") (part "PAD-TEST-POINT'4545'"))
    )
    (comp (ref "TP2")
      (value "PAD-TEST-POINT'4545'")
      (footprint "eagle-import:TP_4545")
      (fields (field (name "PARTNO") "DNP"))
      (libsource (lib "eagle-import") (part "PAD-TEST-POINT'4545'"))
    )
    (comp (ref "TP3")
      (value "PAD-TEST-POINT'4545'")
      (footprint "eagle-import:TP_4545")
      (fields (field (name "PARTNO") "DNP"))
      (libsource (lib "eagle-import") (part "PAD-TEST-POINT'4545'"))
    )
    (comp (ref "U1")
      (value "UCC27524")
      (footprint "eagle-import:SOIC-8")
      (libsource (lib "eagle-import") (part "UCC27524"))
    )
    (comp (ref "U2")
      (value "UCC27524")
      (footprint "eagle-import:SOIC-8")
      (libsource (lib "eagle-import") (part "UCC27524"))
    )
    (comp (ref "C25")
      (value "100p")
      (footprint "eagle-import:C0402")
      (libsource (lib "eagle-import") (part "CAPACITOR_NP_0402"))
    )
    (comp (ref "C26")
      (value ".1u")
      (footprint "eagle-import:C0402")
      (libsource (lib "eagle-import") (part "CAPACITOR_NP_0402"))
    )
    (comp (ref "C27")
      (value ".1u")
      (footprint "eagle-import:C0402")
      (libsource (lib "eagle-import") (part "CAPACITOR_NP_0402"))
    )
    (comp (ref "C28")
      (value "100p")
      (footprint "eagle-import:C0402")
      (libsource (lib "eagle-import") (part "CAPACITOR_NP_0402"))
    )
    (comp (ref "C29")
      (value ".1u")
      (footprint "eagle-import:C0402")
      (libsource (lib "eagle-import") (part "CAPACITOR_NP_0402"))
    )
    (comp (ref "C30")
      (value ".1u")
      (footprint "eagle-import:C0402")
      (libsource (lib "eagle-import") (part "CAPACITOR_NP_0402"))
    )
    (comp (ref "C31")
      (value "100p")
      (footprint "eagle-import:C0402")
      (libsource (lib "eagle-import") (part "CAPACITOR_NP_0402"))
    )
    (comp (ref "C32")
      (value ".1u")
      (footprint "eagle-import:C0402")
      (libsource (lib "eagle-import") (part "CAPACITOR_NP_0402"))
    )
    (comp (ref "C33")
      (value ".1u")
      (footprint "eagle-import:C0402")
      (libsource (lib "eagle-import") (part "CAPACITOR_NP_0402"))
    )
    (comp (ref "C34")
      (value "100p")
      (footprint "eagle-import:C0402")
      (libsource (lib "eagle-import") (part "CAPACITOR_NP_0402"))
    )
    (comp (ref "C35")
      (value ".1u")
      (footprint "eagle-import:C0402")
      (libsource (lib "eagle-import") (part "CAPACITOR_NP_0402"))
    )
    (comp (ref "C36")
      (value ".1u")
      (footprint "eagle-import:C0402")
      (libsource (lib "eagle-import") (part "CAPACITOR_NP_0402"))
    )
    (comp (ref "D9")
      (value "DIODES_SOD-123")
      (footprint "eagle-import:SOD-123")
      (fields (field (name "HOUSEPART") "NO"))
      (libsource (lib "eagle-import") (part "DIODES_SOD-123"))
    )
    (comp (ref "D10")
      (value "DIODES_SOD-123")
      (footprint "eagle-import:SOD-123")
      (fields (field (name "HOUSEPART") "NO"))
      (libsource (lib "eagle-import") (part "DIODES_SOD-123"))
    )
    (comp (ref "D11")
      (value "DIODES_SOD-123")
      (footprint "eagle-import:SOD-123")
      (fields (field (name "HOUSEPART") "NO"))
      (libsource (lib "eagle-import") (part "DIODES_SOD-123"))
    )
    (comp (ref "D12")
      (value "DIODES_SOD-123")
      (footprint "eagle-import:SOD-123")
      (fields (field (name "HOUSEPART") "NO"))
      (libsource (lib "eagle-import") (part "DIODES_SOD-123"))
    )
    (comp (ref "R33")
      (value "100k")
      (footprint "eagle-import:R0402")
      (libsource (lib "eagle-import") (part "RESISTOR_0402"))
    )
    (comp (ref "R34")
      (value "100k")
      (footprint "eagle-import:R0402")
      (libsource (lib "eagle-import") (part "RESISTOR_0402"))
    )
    (comp (ref "R35")
      (value "100k")
      (footprint "eagle-import:R0402")
      (libsource (lib "eagle-import") (part "RESISTOR_0402"))
    )
    (comp (ref "R36")
      (value "1k")
      (footprint "eagle-import:R0402")
      (libsource (lib "eagle-import") (part "RESISTOR_0402"))
    )
    (comp (ref "R37")
      (value "1k")
      (footprint "eagle-import:R0402")
      (libsource (lib "eagle-import") (part "RESISTOR_0402"))
    )
    (comp (ref "R38")
      (value "1k")
      (footprint "eagle-import:R0402")
      (libsource (lib "eagle-import") (part "RESISTOR_0402"))
    )
    (comp (ref "R39")
      (value "1k")
      (footprint "eagle-import:R0402")
      (libsource (lib "eagle-import") (part "RESISTOR_0402"))
    )
    (comp (ref "R40")
      (value "1k")
      (footprint "eagle-import:R0402")
      (libsource (lib "eagle-import") (part "RESISTOR_0402"))
    )
    (comp (ref "R41")
      (value "1k")
      (footprint "eagle-import:R0402")
      (libsource (lib "eagle-import") (part "RESISTOR_0402"))
    )
    (comp (ref "R42")
      (value "1k")
      (footprint "eagle-import:R0402")
      (libsource (lib "eagle-import") (part "RESISTOR_0402"))
    )
    (comp (ref "R43")
      (value "1k")
      (footprint "eagle-import:R0402")
      (libsource (lib "eagle-import") (part "RESISTOR_0402"))
    )
    (comp (ref "R44")
      (value "1k")
      (footprint "eagle-import:R0402")
      (libsource (lib "eagle-import") (part "RESISTOR_0402"))
    )
    (comp (ref "R45")
      (value "100k")
      (footprint "eagle-import:R0402")
      (libsource (lib "eagle-import") (part "RESISTOR_0402"))
    )
    (comp (ref "R46")
      (value "100k")
      (footprint "eagle-import:R0402")
      (libsource (lib "eagle-import") (part "RESISTOR_0402"))
    )
    (comp (ref "R47")
      (value "100k")
      (footprint "eagle-import:R0402")
      (libsource (lib "eagle-import") (part "RESISTOR_0402"))
    )
    (comp (ref "R48")
      (value "100k")
      (footprint "eagle-import:R0402")
      (libsource (lib "eagle-import") (part "RESISTOR_0402"))
    )
    (comp (ref "R49")
      (value "100k")
      (footprint "eagle-import:R0402")
      (libsource (lib "eagle-import") (part "RESISTOR_0402"))
    )
    (comp (ref "R50")
      (value "100k")
      (footprint "eagle-import:R0402")
      (libsource (lib "eagle-import") (part "RESISTOR_0402"))
    )
    (comp (ref "R51")
      (value "1k")
      (footprint "eagle-import:R0402")
      (libsource (lib "eagle-import") (part "RESISTOR_0402"))
    )
    (comp (ref "R52")
      (value "1k")
      (footprint "eagle-import:R0402")
      (libsource (lib "eagle-import") (part "RESISTOR_0402"))
    )
    (comp (ref "R53")
      (value "1k")
      (footprint "eagle-import:R0402")
      (libsource (lib "eagle-import") (part "RESISTOR_0402"))
    )
    (comp (ref "R54")
      (value "1k")
      (footprint "eagle-import:R0402")
      (libsource (lib "eagle-import") (part "RESISTOR_0402"))
    )
    (comp (ref "R55")
      (value "1k")
      (footprint "eagle-import:R0402")
      (libsource (lib "eagle-import") (part "RESISTOR_0402"))
    )
    (comp (ref "R56")
      (value "1k")
      (footprint "eagle-import:R0402")
      (libsource (lib "eagle-import") (part "RESISTOR_0402"))
    )
    (comp (ref "R57")
      (value "100k")
      (footprint "eagle-import:R0402")
      (libsource (lib "eagle-import") (part "RESISTOR_0402"))
    )
    (comp (ref "R58")
      (value "1k")
      (footprint "eagle-import:R0402")
      (libsource (lib "eagle-import") (part "RESISTOR_0402"))
    )
    (comp (ref "R59")
      (value "1k")
      (footprint "eagle-import:R0402")
      (libsource (lib "eagle-import") (part "RESISTOR_0402"))
    )
    (comp (ref "R60")
      (value "1k")
      (footprint "eagle-import:R0402")
      (libsource (lib "eagle-import") (part "RESISTOR_0402"))
    )
    (comp (ref "R61")
      (value "100k")
      (footprint "eagle-import:R0402")
      (libsource (lib "eagle-import") (part "RESISTOR_0402"))
    )
    (comp (ref "R62")
      (value "100k")
      (footprint "eagle-import:R0402")
      (libsource (lib "eagle-import") (part "RESISTOR_0402"))
    )
    (comp (ref "R63")
      (value "1k")
      (footprint "eagle-import:R0402")
      (libsource (lib "eagle-import") (part "RESISTOR_0402"))
    )
    (comp (ref "R64")
      (value "1k")
      (footprint "eagle-import:R0402")
      (libsource (lib "eagle-import") (part "RESISTOR_0402"))
    )
    (comp (ref "U5")
      (value "OPA170")
      (footprint "eagle-import:SOT-23-5")
      (libsource (lib "eagle-import") (part "OPA170"))
    )
    (comp (ref "U6")
      (value "OPA170")
      (footprint "eagle-import:SOT-23-5")
      (libsource (lib "eagle-import") (part "OPA170"))
    )
    (comp (ref "U7")
      (value "OPA170")
      (footprint "eagle-import:SOT-23-5")
      (libsource (lib "eagle-import") (part "OPA170"))
    )
    (comp (ref "U8")
      (value "OPA170")
      (footprint "eagle-import:SOT-23-5")
      (libsource (lib "eagle-import") (part "OPA170"))
    )
    (comp (ref "ADCH")
      (value "8x1F-H8.5")
      (footprint "eagle-import:1X08")
      (libsource (lib "eagle-import") (part "PINHD-1X8"))
    )
    (comp (ref "ADCL")
      (value "8x1F-H8.5")
      (footprint "eagle-import:1X08")
      (libsource (lib "eagle-import") (part "PINHD-1X8"))
    )
    (comp (ref "C49")
      (value ".1u")
      (footprint "eagle-import:C0402")
      (libsource (lib "eagle-import") (part "CAPACITOR_NP_0402"))
    )
    (comp (ref "C50")
      (value "33u")
      (footprint "eagle-import:CP1206")
      (libsource (lib "eagle-import") (part "CAPACITOR_P"))
    )
    (comp (ref "C51")
      (value ".1u")
      (footprint "eagle-import:C0402")
      (libsource (lib "eagle-import") (part "CAPACITOR_NP_0402"))
    )
    (comp (ref "C52")
      (value "22p")
      (footprint "eagle-import:C0402")
      (libsource (lib "eagle-import") (part "CAPACITOR_NP_0402"))
    )
    (comp (ref "C53")
      (value "22p")
      (footprint "eagle-import:C0402")
      (libsource (lib "eagle-import") (part "CAPACITOR_NP_0402"))
    )
    (comp (ref "COMMUNICATION")
      (value "8x1F-H8.5")
      (footprint "eagle-import:1X08")
      (libsource (lib "eagle-import") (part "PINHD-1X8"))
    )
    (comp (ref "CON9")
      (value "CON3")
      (footprint "eagle-import:PHOENIX_3_45")
      (libsource (lib "eagle-import") (part "CON3"))
    )
    (comp (ref "CON10")
      (value "CON3")
      (footprint "eagle-import:PHOENIX_3_45")
      (libsource (lib "eagle-import") (part "CON3"))
    )
    (comp (ref "CON12")
      (value "CON23.5MM")
      (footprint "eagle-import:PHOENIX_2_45")
      (libsource (lib "eagle-import") (part "CON23.5MM"))
    )
    (comp (ref "CON14")
      (value "CON23.5MM")
      (footprint "eagle-import:PHOENIX_2_45")
      (libsource (lib "eagle-import") (part "CON23.5MM"))
    )
    (comp (ref "CON15")
      (value "CON5")
      (footprint "eagle-import:PHOENIX_5_45")
      (libsource (lib "eagle-import") (part "CON5"))
    )
    (comp (ref "CON16")
      (value "CON23.5MM")
      (footprint "eagle-import:PHOENIX_2_45")
      (fields (field (name "MFG") "PHOENIXCONTACT") (field (name "PARTNO") "1773976"))
      (libsource (lib "eagle-import") (part "CON23.5MM"))
    )
    (comp (ref "D17")
      (value "LED_SINGLE-0603")
      (footprint "eagle-import:LED0603")
      (fields (field (name "HOUSEPART") "NO"))
      (libsource (lib "eagle-import") (part "LED_SINGLE-0603"))
    )
    (comp (ref "D18")
      (value "Green")
      (footprint "eagle-import:LED0603")
      (fields (field (name "HOUSEPART") "NO"))
      (libsource (lib "eagle-import") (part "LED_SINGLE-0603"))
    )
    (comp (ref "D19")
      (value "Green")
      (footprint "eagle-import:LED0603")
      (fields (field (name "HOUSEPART") "NO"))
      (libsource (lib "eagle-import") (part "LED_SINGLE-0603"))
    )
    (comp (ref "D20")
      (value "Red")
      (footprint "eagle-import:LED0603")
      (fields (field (name "HOUSEPART") "NO"))
      (libsource (lib "eagle-import") (part "LED_SINGLE-0603"))
    )
    (comp (ref "D21")
      (value "Blue")
      (footprint "eagle-import:LED0603")
      (fields (field (name "HOUSEPART") "NO"))
      (libsource (lib "eagle-import") (part "LED_SINGLE-0603"))
    )
    (comp (ref "JP1")
      (value "10x1F-H8.5")
      (footprint "eagle-import:1X10")
      (libsource (lib "eagle-import") (part "PINHD-1X10_ARD"))
    )
    (comp (ref "JP2")
      (value "JP1E")
      (footprint "eagle-import:JP1")
      (libsource (lib "eagle-import") (part "JP1E"))
    )
    (comp (ref "POWER")
      (value "8x1F-H8.5")
      (footprint "eagle-import:1X08")
      (libsource (lib "eagle-import") (part "PINHD-1X8"))
    )
    (comp (ref "PWML")
      (value "8x1F-H8.5")
      (footprint "eagle-import:1X08")
      (libsource (lib "eagle-import") (part "PINHD-1X8"))
    )
    (comp (ref "Q10")
      (value "RE1C002UN")
      (footprint "eagle-import:EMT3F")
      (libsource (lib "eagle-import") (part "RE1C002UN"))
    )
    (comp (ref "R97")
      (value "1k")
      (footprint "eagle-import:R0402")
      (libsource (lib "eagle-import") (part "RESISTOR_0402"))
    )
    (comp (ref "R98")
      (value "1k")
      (footprint "eagle-import:R0402")
      (libsource (lib "eagle-import") (part "RESISTOR_0402"))
    )
    (comp (ref "R99")
      (value "1k")
      (footprint "eagle-import:R0402")
      (libsource (lib "eagle-import") (part "RESISTOR_0402"))
    )
    (comp (ref "R100")
      (value "1k")
      (footprint "eagle-import:R0402")
      (libsource (lib "eagle-import") (part "RESISTOR_0402"))
    )
    (comp (ref "R101")
      (value ".3")
      (footprint "eagle-import:R0402")
      (libsource (lib "eagle-import") (part "RESISTOR_0402"))
    )
    (comp (ref "R102")
      (value "120")
      (footprint "eagle-import:R0402")
      (libsource (lib "eagle-import") (part "RESISTOR_0402"))
    )
    (comp (ref "R103")
      (value "1k")
      (footprint "eagle-import:R0402")
      (libsource (lib "eagle-import") (part "RESISTOR_0402"))
    )
    (comp (ref "R104")
      (value "10k")
      (footprint "eagle-import:R0402")
      (libsource (lib "eagle-import") (part "RESISTOR_0402"))
    )
    (comp (ref "R105")
      (value "47k")
      (footprint "eagle-import:R0402")
      (libsource (lib "eagle-import") (part "RESISTOR_0402"))
    )
    (comp (ref "R106")
      (value "0")
      (footprint "eagle-import:R0402")
      (libsource (lib "eagle-import") (part "RESISTOR_0402"))
    )
    (comp (ref "R107")
      (value "0")
      (footprint "eagle-import:R0402")
      (libsource (lib "eagle-import") (part "RESISTOR_0402"))
    )
    (comp (ref "R108")
      (value "0")
      (footprint "eagle-import:R0402")
      (libsource (lib "eagle-import") (part "RESISTOR_0402"))
    )
    (comp (ref "R109")
      (value "0")
      (footprint "eagle-import:R0402")
      (libsource (lib "eagle-import") (part "RESISTOR_0402"))
    )
    (comp (ref "R110")
      (value "0")
      (footprint "eagle-import:R0402")
      (libsource (lib "eagle-import") (part "RESISTOR_0402"))
    )
    (comp (ref "R111")
      (value "DNP")
      (footprint "eagle-import:R0402")
      (libsource (lib "eagle-import") (part "RESISTOR_0402"))
    )
    (comp (ref "R112")
      (value "DNP")
      (footprint "eagle-import:R0402")
      (libsource (lib "eagle-import") (part "RESISTOR_0402"))
    )
    (comp (ref "R113")
      (value "DNP")
      (footprint "eagle-import:R0402")
      (libsource (lib "eagle-import") (part "RESISTOR_0402"))
    )
    (comp (ref "R114")
      (value "DNP")
      (footprint "eagle-import:R0402")
      (libsource (lib "eagle-import") (part "RESISTOR_0402"))
    )
    (comp (ref "R115")
      (value "DNP")
      (footprint "eagle-import:R0402")
      (libsource (lib "eagle-import") (part "RESISTOR_0402"))
    )
    (comp (ref "RELAY1")
      (value "RELAY_DPDT")
      (footprint "eagle-import:KEMET_EE2")
      (fields (field (name "PARTNO") "EE2-5NU-L"))
      (libsource (lib "eagle-import") (part "RELAY_DPDT"))
    )
    (comp (ref "U13")
      (value "TL750M")
      (footprint "eagle-import:TO-263")
      (libsource (lib "eagle-import") (part "TL750M"))
    )
    (comp (ref "U14")
      (value "MCP2551")
      (footprint "eagle-import:SOIC8-6.0")
      (libsource (lib "eagle-import") (part "MCP2551-SOIC8"))
    )
    (comp (ref "U15")
      (value "MCP2515")
      (footprint "eagle-import:SOIC18")
      (libsource (lib "eagle-import") (part "MCP2515-SOIC18"))
    )
    (comp (ref "X1")
      (value "16MHz")
      (footprint "eagle-import:HC49UP")
      (libsource (lib "eagle-import") (part "CRYSTAL-HC49UP"))
    )
    (comp (ref "XIO")
      (value "18x2F-H8.5")
      (footprint "eagle-import:2X18")
      (libsource (lib "eagle-import") (part "PINHD-2X18"))
    )
    (comp (ref "C37")
      (value "100p")
      (footprint "eagle-import:C0402")
      (libsource (lib "eagle-import") (part "CAPACITOR_NP_0402"))
    )
    (comp (ref "C38")
      (value ".1u")
      (footprint "eagle-import:C0402")
      (libsource (lib "eagle-import") (part "CAPACITOR_NP_0402"))
    )
    (comp (ref "C39")
      (value ".1u")
      (footprint "eagle-import:C0402")
      (libsource (lib "eagle-import") (part "CAPACITOR_NP_0402"))
    )
    (comp (ref "C40")
      (value "100p")
      (footprint "eagle-import:C0402")
      (libsource (lib "eagle-import") (part "CAPACITOR_NP_0402"))
    )
    (comp (ref "C41")
      (value ".1u")
      (footprint "eagle-import:C0402")
      (libsource (lib "eagle-import") (part "CAPACITOR_NP_0402"))
    )
    (comp (ref "C42")
      (value ".1u")
      (footprint "eagle-import:C0402")
      (libsource (lib "eagle-import") (part "CAPACITOR_NP_0402"))
    )
    (comp (ref "C43")
      (value "100p")
      (footprint "eagle-import:C0402")
      (libsource (lib "eagle-import") (part "CAPACITOR_NP_0402"))
    )
    (comp (ref "C44")
      (value ".1u")
      (footprint "eagle-import:C0402")
      (libsource (lib "eagle-import") (part "CAPACITOR_NP_0402"))
    )
    (comp (ref "C45")
      (value ".1u")
      (footprint "eagle-import:C0402")
      (libsource (lib "eagle-import") (part "CAPACITOR_NP_0402"))
    )
    (comp (ref "C46")
      (value "100p")
      (footprint "eagle-import:C0402")
      (libsource (lib "eagle-import") (part "CAPACITOR_NP_0402"))
    )
    (comp (ref "C47")
      (value ".1u")
      (footprint "eagle-import:C0402")
      (libsource (lib "eagle-import") (part "CAPACITOR_NP_0402"))
    )
    (comp (ref "C48")
      (value ".1u")
      (footprint "eagle-import:C0402")
      (libsource (lib "eagle-import") (part "CAPACITOR_NP_0402"))
    )
    (comp (ref "D13")
      (value "DIODES_SOD-123")
      (footprint "eagle-import:SOD-123")
      (fields (field (name "HOUSEPART") "NO"))
      (libsource (lib "eagle-import") (part "DIODES_SOD-123"))
    )
    (comp (ref "D14")
      (value "DIODES_SOD-123")
      (footprint "eagle-import:SOD-123")
      (fields (field (name "HOUSEPART") "NO"))
      (libsource (lib "eagle-import") (part "DIODES_SOD-123"))
    )
    (comp (ref "D15")
      (value "DIODES_SOD-123")
      (footprint "eagle-import:SOD-123")
      (fields (field (name "HOUSEPART") "NO"))
      (libsource (lib "eagle-import") (part "DIODES_SOD-123"))
    )
    (comp (ref "D16")
      (value "DIODES_SOD-123")
      (footprint "eagle-import:SOD-123")
      (fields (field (name "HOUSEPART") "NO"))
      (libsource (lib "eagle-import") (part "DIODES_SOD-123"))
    )
    (comp (ref "R65")
      (value "100k")
      (footprint "eagle-import:R0402")
      (libsource (lib "eagle-import") (part "RESISTOR_0402"))
    )
    (comp (ref "R66")
      (value "100k")
      (footprint "eagle-import:R0402")
      (libsource (lib "eagle-import") (part "RESISTOR_0402"))
    )
    (comp (ref "R67")
      (value "100k")
      (footprint "eagle-import:R0402")
      (libsource (lib "eagle-import") (part "RESISTOR_0402"))
    )
    (comp (ref "R68")
      (value "1k")
      (footprint "eagle-import:R0402")
      (libsource (lib "eagle-import") (part "RESISTOR_0402"))
    )
    (comp (ref "R69")
      (value "1k")
      (footprint "eagle-import:R0402")
      (libsource (lib "eagle-import") (part "RESISTOR_0402"))
    )
    (comp (ref "R70")
      (value "1k")
      (footprint "eagle-import:R0402")
      (libsource (lib "eagle-import") (part "RESISTOR_0402"))
    )
    (comp (ref "R71")
      (value "1k")
      (footprint "eagle-import:R0402")
      (libsource (lib "eagle-import") (part "RESISTOR_0402"))
    )
    (comp (ref "R72")
      (value "1k")
      (footprint "eagle-import:R0402")
      (libsource (lib "eagle-import") (part "RESISTOR_0402"))
    )
    (comp (ref "R73")
      (value "1k")
      (footprint "eagle-import:R0402")
      (libsource (lib "eagle-import") (part "RESISTOR_0402"))
    )
    (comp (ref "R74")
      (value "1k")
      (footprint "eagle-import:R0402")
      (libsource (lib "eagle-import") (part "RESISTOR_0402"))
    )
    (comp (ref "R75")
      (value "1k")
      (footprint "eagle-import:R0402")
      (libsource (lib "eagle-import") (part "RESISTOR_0402"))
    )
    (comp (ref "R76")
      (value "1k")
      (footprint "eagle-import:R0402")
      (libsource (lib "eagle-import") (part "RESISTOR_0402"))
    )
    (comp (ref "R77")
      (value "100k")
      (footprint "eagle-import:R0402")
      (libsource (lib "eagle-import") (part "RESISTOR_0402"))
    )
    (comp (ref "R78")
      (value "100k")
      (footprint "eagle-import:R0402")
      (libsource (lib "eagle-import") (part "RESISTOR_0402"))
    )
    (comp (ref "R79")
      (value "100k")
      (footprint "eagle-import:R0402")
      (libsource (lib "eagle-import") (part "RESISTOR_0402"))
    )
    (comp (ref "R80")
      (value "100k")
      (footprint "eagle-import:R0402")
      (libsource (lib "eagle-import") (part "RESISTOR_0402"))
    )
    (comp (ref "R81")
      (value "100k")
      (footprint "eagle-import:R0402")
      (libsource (lib "eagle-import") (part "RESISTOR_0402"))
    )
    (comp (ref "R82")
      (value "100k")
      (footprint "eagle-import:R0402")
      (libsource (lib "eagle-import") (part "RESISTOR_0402"))
    )
    (comp (ref "R83")
      (value "1k")
      (footprint "eagle-import:R0402")
      (libsource (lib "eagle-import") (part "RESISTOR_0402"))
    )
    (comp (ref "R84")
      (value "1k")
      (footprint "eagle-import:R0402")
      (libsource (lib "eagle-import") (part "RESISTOR_0402"))
    )
    (comp (ref "R85")
      (value "1k")
      (footprint "eagle-import:R0402")
      (libsource (lib "eagle-import") (part "RESISTOR_0402"))
    )
    (comp (ref "R86")
      (value "1k")
      (footprint "eagle-import:R0402")
      (libsource (lib "eagle-import") (part "RESISTOR_0402"))
    )
    (comp (ref "R87")
      (value "1k")
      (footprint "eagle-import:R0402")
      (libsource (lib "eagle-import") (part "RESISTOR_0402"))
    )
    (comp (ref "R88")
      (value "1k")
      (footprint "eagle-import:R0402")
      (libsource (lib "eagle-import") (part "RESISTOR_0402"))
    )
    (comp (ref "R89")
      (value "100k")
      (footprint "eagle-import:R0402")
      (libsource (lib "eagle-import") (part "RESISTOR_0402"))
    )
    (comp (ref "R90")
      (value "1k")
      (footprint "eagle-import:R0402")
      (libsource (lib "eagle-import") (part "RESISTOR_0402"))
    )
    (comp (ref "R91")
      (value "1k")
      (footprint "eagle-import:R0402")
      (libsource (lib "eagle-import") (part "RESISTOR_0402"))
    )
    (comp (ref "R92")
      (value "1k")
      (footprint "eagle-import:R0402")
      (libsource (lib "eagle-import") (part "RESISTOR_0402"))
    )
    (comp (ref "R93")
      (value "100k")
      (footprint "eagle-import:R0402")
      (libsource (lib "eagle-import") (part "RESISTOR_0402"))
    )
    (comp (ref "R94")
      (value "100k")
      (footprint "eagle-import:R0402")
      (libsource (lib "eagle-import") (part "RESISTOR_0402"))
    )
    (comp (ref "R95")
      (value "1k")
      (footprint "eagle-import:R0402")
      (libsource (lib "eagle-import") (part "RESISTOR_0402"))
    )
    (comp (ref "R96")
      (value "1k")
      (footprint "eagle-import:R0402")
      (libsource (lib "eagle-import") (part "RESISTOR_0402"))
    )
    (comp (ref "U9")
      (value "OPA170")
      (footprint "eagle-import:SOT-23-5")
      (libsource (lib "eagle-import") (part "OPA170"))
    )
    (comp (ref "U10")
      (value "OPA170")
      (footprint "eagle-import:SOT-23-5")
      (libsource (lib "eagle-import") (part "OPA170"))
    )
    (comp (ref "U11")
      (value "OPA170")
      (footprint "eagle-import:SOT-23-5")
      (libsource (lib "eagle-import") (part "OPA170"))
    )
    (comp (ref "U12")
      (value "OPA170")
      (footprint "eagle-import:SOT-23-5")
      (libsource (lib "eagle-import") (part "OPA170"))
    )
    (comp (ref "CON11")
      (value "CON210.16MM")
      (footprint "eagle-import:PHOENIX_2_10.16MM")
      (fields (field (name "MFG") "PHOENIXCONTACT") (field (name "PARTNO") "1773976"))
      (libsource (lib "eagle-import") (part "CON210.16MM"))
    )
    (comp (ref "CON13")
      (value "CON3")
      (footprint "eagle-import:PHOENIX_3_45")
      (libsource (lib "eagle-import") (part "CON3"))
    )
    (comp (ref "CON17")
      (value "CON210.16MM")
      (footprint "eagle-import:PHOENIX_2_10.16MM")
      (fields (field (name "MFG") "PHOENIXCONTACT") (field (name "PARTNO") "1773976"))
      (libsource (lib "eagle-import") (part "CON210.16MM"))
    )
    (comp (ref "F3")
      (value "40A")
      (footprint "eagle-import:FUSE_ATO")
      (fields (field (name "MFG") "Littelfuse") (field (name "PARTNO") "178.6165.0001"))
      (libsource (lib "eagle-import") (part "FUSE"))
    )
    (comp (ref "Q9")
      (value "N-CHANNEL_FET_SOT-23-3")
      (footprint "eagle-import:SOT-23-3")
      (fields (field (name "HOUSEPART") "NO"))
      (libsource (lib "eagle-import") (part "N-CHANNEL_FET_SOT-23-3"))
    )
    (comp (ref "Q11")
      (value "N-CHANNEL_FET_SOT-23-3")
      (footprint "eagle-import:SOT-23-3")
      (fields (field (name "HOUSEPART") "NO"))
      (libsource (lib "eagle-import") (part "N-CHANNEL_FET_SOT-23-3"))
    )
    (comp (ref "Q12")
      (value "N-CHANNEL_FET_SOT-23-3")
      (footprint "eagle-import:SOT-23-3")
      (fields (field (name "HOUSEPART") "NO"))
      (libsource (lib "eagle-import") (part "N-CHANNEL_FET_SOT-23-3"))
    )
    (comp (ref "R116")
      (value "1k")
      (footprint "eagle-import:R0402")
      (libsource (lib "eagle-import") (part "RESISTOR_0402"))
    )
    (comp (ref "R117")
      (value "1k")
      (footprint "eagle-import:R0402")
      (libsource (lib "eagle-import") (part "RESISTOR_0402"))
    )
    (comp (ref "R118")
      (value "5.1k")
      (footprint "eagle-import:R0402")
      (libsource (lib "eagle-import") (part "RESISTOR_0402"))
    )
    (comp (ref "R119")
      (value "1k")
      (footprint "eagle-import:R0402")
      (libsource (lib "eagle-import") (part "RESISTOR_0402"))
    )
    (comp (ref "RELAY2")
      (value "RELAY_BOM")
      (footprint "eagle-import:VCF4_RELAY")
      (fields (field (name "MFG") "TE") (field (name "PARTNO") "1432868-1"))
      (libsource (lib "eagle-import") (part "RELAY_BOM"))
    )
    (comp (ref "RELAY3")
      (value "RELAY_VF4")
      (footprint "eagle-import:VCF4-SOCKET")
      (fields (field (name "MFG") "TE") (field (name "PARTNO") "VCF4-1000"))
      (libsource (lib "eagle-import") (part "RELAY_VF4"))
    )
  )
  (nets
    (net (code "1") (name "+3V3") (class "Default")
      (node (ref "POWER") (pin "4") (pinfunction "4_4") (pintype "passive"))
    )
    (net (code "2") (name "+5V") (class "Default")
      (node (ref "C26") (pin "P$1") (pinfunction "P$1_P$1") (pintype "passive"))
      (node (ref "C29") (pin "P$1") (pinfunction "P$1_P$1") (pintype "passive"))
      (node (ref "C32") (pin "P$1") (pinfunction "P$1_P$1") (pintype "passive"))
      (node (ref "C35") (pin "P$1") (pinfunction "P$1_P$1") (pintype "passive"))
      (node (ref "C38") (pin "P$1") (pinfunction "P$1_P$1") (pintype "passive"))
      (node (ref "C41") (pin "P$1") (pinfunction "P$1_P$1") (pintype "passive"))
      (node (ref "C44") (pin "P$1") (pinfunction "P$1_P$1") (pintype "passive"))
      (node (ref "C47") (pin "P$1") (pinfunction "P$1_P$1") (pintype "passive"))
      (node (ref "C49") (pin "P$1") (pinfunction "P$1_P$1") (pintype "passive"))
      (node (ref "C51") (pin "P$1") (pinfunction "P$1_P$1") (pintype "passive"))
      (node (ref "CON12") (pin "P$1") (pinfunction "P$1_P$1") (pintype "bidirectional"))
      (node (ref "POWER") (pin "2") (pinfunction "2_2") (pintype "passive"))
      (node (ref "POWER") (pin "5") (pinfunction "5_5") (pintype "passive"))
      (node (ref "R100") (pin "P$2") (pinfunction "P$2_P$2") (pintype "passive"))
      (node (ref "R101") (pin "P$1") (pinfunction "P$1_P$1") (pintype "passive"))
      (node (ref "R103") (pin "P$2") (pinfunction "P$2_P$2") (pintype "passive"))
      (node (ref "R104") (pin "P$1") (pinfunction "P$1_P$1") (pintype "passive"))
      (node (ref "R97") (pin "P$2") (pinfunction "P$2_P$2") (pintype "passive"))
      (node (ref "R98") (pin "P$2") (pinfunction "P$2_P$2") (pintype "passive"))
      (node (ref "R99") (pin "P$2") (pinfunction "P$2_P$2") (pintype "passive"))
      (node (ref "RELAY1") (pin "P$1") (pinfunction "P$1_P$1") (pintype "bidirectional"))
      (node (ref "U10") (pin "P$5") (pinfunction "V+_P$5") (pintype "bidirectional"))
      (node (ref "U11") (pin "P$5") (pinfunction "V+_P$5") (pintype "bidirectional"))
      (node (ref "U12") (pin "P$5") (pinfunction "V+_P$5") (pintype "bidirectional"))
      (node (ref "U13") (pin "P$3") (pinfunction "VOUT_P$3") (pintype "bidirectional"))
      (node (ref "U14") (pin "3") (pinfunction "VDD_3") (pintype "bidirectional"))
      (node (ref "U15") (pin "18") (pinfunction "VDD_18") (pintype "power_in"))
      (node (ref "U5") (pin "P$5") (pinfunction "V+_P$5") (pintype "bidirectional"))
      (node (ref "U6") (pin "P$5") (pinfunction "V+_P$5") (pintype "bidirectional"))
      (node (ref "U7") (pin "P$5") (pinfunction "V+_P$5") (pintype "bidirectional"))
      (node (ref "U8") (pin "P$5") (pinfunction "V+_P$5") (pintype "bidirectional"))
      (node (ref "U9") (pin "P$5") (pinfunction "V+_P$5") (pintype "bidirectional"))
    )
    (net (code "3") (name "ADC9") (class "Default")
      (node (ref "ADCH") (pin "2") (pinfunction "2_2") (pintype "passive"))
      (node (ref "R106") (pin "P$1") (pinfunction "P$1_P$1") (pintype "passive"))
      (node (ref "R115") (pin "P$1") (pinfunction "P$1_P$1") (pintype "passive"))
    )
    (net (code "4") (name "ADC10") (class "Default")
      (node (ref "ADCH") (pin "3") (pinfunction "3_3") (pintype "passive"))
      (node (ref "R107") (pin "P$1") (pinfunction "P$1_P$1") (pintype "passive"))
      (node (ref "R114") (pin "P$1") (pinfunction "P$1_P$1") (pintype "passive"))
    )
    (net (code "5") (name "ADC11") (class "Default")
      (node (ref "ADCH") (pin "4") (pinfunction "4_4") (pintype "passive"))
      (node (ref "R108") (pin "P$1") (pinfunction "P$1_P$1") (pintype "passive"))
      (node (ref "R113") (pin "P$1") (pinfunction "P$1_P$1") (pintype "passive"))
    )
    (net (code "6") (name "ADC12") (class "Default")
      (node (ref "ADCH") (pin "5") (pinfunction "5_5") (pintype "passive"))
      (node (ref "R120") (pin "P$2") (pinfunction "P$2_P$2") (pintype "passive"))
      (node (ref "R121") (pin "P$1") (pinfunction "P$1_P$1") (pintype "passive"))
    )
    (net (code "7") (name "ADC13") (class "Default")
      (node (ref "ADCH") (pin "6") (pinfunction "6_6") (pintype "passive"))
      (node (ref "R109") (pin "P$1") (pinfunction "P$1_P$1") (pintype "passive"))
      (node (ref "R112") (pin "P$1") (pinfunction "P$1_P$1") (pintype "passive"))
    )
    (net (code "8") (name "ADC14") (class "Default")
      (node (ref "ADCH") (pin "7") (pinfunction "7_7") (pintype "passive"))
      (node (ref "R110") (pin "P$1") (pinfunction "P$1_P$1") (pintype "passive"))
      (node (ref "R111") (pin "P$1") (pinfunction "P$1_P$1") (pintype "passive"))
    )
    (net (code "9") (name "ADC15") (class "Default")
      (node (ref "ADCH") (pin "8") (pinfunction "8_8") (pintype "passive"))
    )
    (net (code "10") (name "AREF") (class "Default")
      (node (ref "JP1") (pin "3") (pinfunction "3_3") (pintype "passive"))
    )
    (net (code "11") (name "CANH") (class "Default")
      (node (ref "CON14") (pin "P$1") (pinfunction "P$1_P$1") (pintype "bidirectional"))
      (node (ref "JP2") (pin "1") (pinfunction "1_1") (pintype "passive"))
      (node (ref "U14") (pin "7") (pinfunction "CANH_7") (pintype "bidirectional"))
    )
    (net (code "12") (name "CANL") (class "Default")
      (node (ref "CON14") (pin "P$2") (pinfunction "P$2_P$2") (pintype "bidirectional"))
      (node (ref "R102") (pin "P$1") (pinfunction "P$1_P$1") (pintype "passive"))
      (node (ref "U14") (pin "6") (pinfunction "CANL_6") (pintype "bidirectional"))
    )
    (net (code "13") (name "CS") (class "Default")
      (node (ref "U15") (pin "16") (pinfunction "~{CS}_16") (pintype "input"))
      (node (ref "XIO") (pin "34") (pinfunction "34_34") (pintype "passive"))
    )
    (net (code "14") (name "GND") (class "Default")
      (node (ref "C1") (pin "P$2") (pinfunction "P$2_P$2") (pintype "passive"))
      (node (ref "C10") (pin "P$2") (pinfunction "P$2_P$2") (pintype "passive"))
      (node (ref "C11") (pin "P$2") (pinfunction "P$2_P$2") (pintype "passive"))
      (node (ref "C12") (pin "P$2") (pinfunction "P$2_P$2") (pintype "passive"))
      (node (ref "C13") (pin "P$2") (pinfunction "P$2_P$2") (pintype "passive"))
      (node (ref "C14") (pin "P$2") (pinfunction "P$2_P$2") (pintype "passive"))
      (node (ref "C15") (pin "P$2") (pinfunction "P$2_P$2") (pintype "passive"))
      (node (ref "C16") (pin "P$2") (pinfunction "P$2_P$2") (pintype "passive"))
      (node (ref "C17") (pin "P$2") (pinfunction "P$2_P$2") (pintype "passive"))
      (node (ref "C18") (pin "P$2") (pinfunction "P$2_P$2") (pintype "passive"))
      (node (ref "C2") (pin "P$2") (pinfunction "P$2_P$2") (pintype "passive"))
      (node (ref "C23") (pin "P$2") (pinfunction "P$2_P$2") (pintype "passive"))
      (node (ref "C24") (pin "P$2") (pinfunction "P$2_P$2") (pintype "passive"))
      (node (ref "C26") (pin "P$2") (pinfunction "P$2_P$2") (pintype "passive"))
      (node (ref "C27") (pin "P$2") (pinfunction "P$2_P$2") (pintype "passive"))
      (node (ref "C29") (pin "P$2") (pinfunction "P$2_P$2") (pintype "passive"))
      (node (ref "C30") (pin "P$2") (pinfunction "P$2_P$2") (pintype "passive"))
      (node (ref "C32") (pin "P$2") (pinfunction "P$2_P$2") (pintype "passive"))
      (node (ref "C33") (pin "P$2") (pinfunction "P$2_P$2") (pintype "passive"))
      (node (ref "C35") (pin "P$2") (pinfunction "P$2_P$2") (pintype "passive"))
      (node (ref "C36") (pin "P$2") (pinfunction "P$2_P$2") (pintype "passive"))
      (node (ref "C38") (pin "P$2") (pinfunction "P$2_P$2") (pintype "passive"))
      (node (ref "C39") (pin "P$2") (pinfunction "P$2_P$2") (pintype "passive"))
      (node (ref "C41") (pin "P$2") (pinfunction "P$2_P$2") (pintype "passive"))
      (node (ref "C42") (pin "P$2") (pinfunction "P$2_P$2") (pintype "passive"))
      (node (ref "C44") (pin "P$2") (pinfunction "P$2_P$2") (pintype "passive"))
      (node (ref "C45") (pin "P$2") (pinfunction "P$2_P$2") (pintype "passive"))
      (node (ref "C47") (pin "P$2") (pinfunction "P$2_P$2") (pintype "passive"))
      (node (ref "C48") (pin "P$2") (pinfunction "P$2_P$2") (pintype "passive"))
      (node (ref "C49") (pin "P$2") (pinfunction "P$2_P$2") (pintype "passive"))
      (node (ref "C5") (pin "P$2") (pinfunction "P$2_P$2") (pintype "passive"))
      (node (ref "C50") (pin "P$2") (pinfunction "P$2_P$2") (pintype "passive"))
      (node (ref "C51") (pin "P$2") (pinfunction "P$2_P$2") (pintype "passive"))
      (node (ref "C52") (pin "P$1") (pinfunction "P$1_P$1") (pintype "passive"))
      (node (ref "C53") (pin "P$1") (pinfunction "P$1_P$1") (pintype "passive"))
      (node (ref "C6") (pin "P$2") (pinfunction "P$2_P$2") (pintype "passive"))
      (node (ref "C9") (pin "P$2") (pinfunction "P$2_P$2") (pintype "passive"))
      (node (ref "CON11") (pin "P$3") (pinfunction "P$2_P$3") (pintype "bidirectional"))
      (node (ref "CON11") (pin "P$4") (pinfunction "P$2_P$4") (pintype "bidirectional"))
      (node (ref "CON12") (pin "P$2") (pinfunction "P$2_P$2") (pintype "bidirectional"))
      (node (ref "CON16") (pin "P$1") (pinfunction "P$1_P$1") (pintype "bidirectional"))
      (node (ref "CON17") (pin "P$1") (pinfunction "P$1_P$1") (pintype "bidirectional"))
      (node (ref "CON17") (pin "P$2") (pinfunction "P$1_P$2") (pintype "bidirectional"))
      (node (ref "D18") (pin "CATHODE") (pinfunction "CATHODE_CATHODE") (pintype "power_in"))
      (node (ref "JP1") (pin "4") (pinfunction "4_4") (pintype "passive"))
      (node (ref "POWER") (pin "6") (pinfunction "6_6") (pintype "passive"))
      (node (ref "POWER") (pin "7") (pinfunction "7_7") (pintype "passive"))
      (node (ref "Q10") (pin "P$2") (pinfunction "S_P$2") (pintype "passive"))
      (node (ref "Q11") (pin "P$2") (pinfunction "SOURCE_P$2") (pintype "bidirectional"))
      (node (ref "Q12") (pin "P$2") (pinfunction "SOURCE_P$2") (pintype "bidirectional"))
      (node (ref "Q9") (pin "P$2") (pinfunction "SOURCE_P$2") (pintype "bidirectional"))
      (node (ref "R1") (pin "P$2") (pinfunction "P$2_P$2") (pintype "passive"))
      (node (ref "R10") (pin "P$1") (pinfunction "P$1_P$1") (pintype "passive"))
      (node (ref "R105") (pin "P$2") (pinfunction "P$2_P$2") (pintype "passive"))
      (node (ref "R111") (pin "P$2") (pinfunction "P$2_P$2") (pintype "passive"))
      (node (ref "R112") (pin "P$2") (pinfunction "P$2_P$2") (pintype "passive"))
      (node (ref "R113") (pin "P$2") (pinfunction "P$2_P$2") (pintype "passive"))
      (node (ref "R114") (pin "P$2") (pinfunction "P$2_P$2") (pintype "passive"))
      (node (ref "R115") (pin "P$2") (pinfunction "P$2_P$2") (pintype "passive"))
      (node (ref "R116") (pin "P$2") (pinfunction "P$2_P$2") (pintype "passive"))
      (node (ref "R121") (pin "P$2") (pinfunction "P$2_P$2") (pintype "passive"))
      (node (ref "R13") (pin "P$2") (pinfunction "P$2_P$2") (pintype "passive"))
      (node (ref "R14") (pin "P$2") (pinfunction "P$2_P$2") (pintype "passive"))
      (node (ref "R15") (pin "P$1") (pinfunction "P$1_P$1") (pintype "passive"))
      (node (ref "R16") (pin "P$1") (pinfunction "P$1_P$1") (pintype "passive"))
      (node (ref "R17") (pin "P$2") (pinfunction "P$2_P$2") (pintype "passive"))
      (node (ref "R18") (pin "P$2") (pinfunction "P$2_P$2") (pintype "passive"))
      (node (ref "R19") (pin "P$2") (pinfunction "P$2_P$2") (pintype "passive"))
      (node (ref "R2") (pin "P$2") (pinfunction "P$2_P$2") (pintype "passive"))
      (node (ref "R20") (pin "P$2") (pinfunction "P$2_P$2") (pintype "passive"))
      (node (ref "R29") (pin "P$1") (pinfunction "P$1_P$1") (pintype "passive"))
      (node (ref "R30") (pin "P$1") (pinfunction "P$1_P$1") (pintype "passive"))
      (node (ref "R31") (pin "P$1") (pinfunction "P$1_P$1") (pintype "passive"))
      (node (ref "R32") (pin "P$1") (pinfunction "P$1_P$1") (pintype "passive"))
      (node (ref "R33") (pin "P$1") (pinfunction "P$1_P$1") (pintype "passive"))
      (node (ref "R34") (pin "P$1") (pinfunction "P$1_P$1") (pintype "passive"))
      (node (ref "R35") (pin "P$1") (pinfunction "P$1_P$1") (pintype "passive"))
      (node (ref "R45") (pin "P$1") (pinfunction "P$1_P$1") (pintype "passive"))
      (node (ref "R46") (pin "P$1") (pinfunction "P$1_P$1") (pintype "passive"))
      (node (ref "R47") (pin "P$1") (pinfunction "P$1_P$1") (pintype "passive"))
      (node (ref "R57") (pin "P$1") (pinfunction "P$1_P$1") (pintype "passive"))
      (node (ref "R61") (pin "P$1") (pinfunction "P$1_P$1") (pintype "passive"))
      (node (ref "R65") (pin "P$1") (pinfunction "P$1_P$1") (pintype "passive"))
      (node (ref "R66") (pin "P$1") (pinfunction "P$1_P$1") (pintype "passive"))
      (node (ref "R67") (pin "P$1") (pinfunction "P$1_P$1") (pintype "passive"))
      (node (ref "R77") (pin "P$1") (pinfunction "P$1_P$1") (pintype "passive"))
      (node (ref "R78") (pin "P$1") (pinfunction "P$1_P$1") (pintype "passive"))
      (node (ref "R79") (pin "P$1") (pinfunction "P$1_P$1") (pintype "passive"))
      (node (ref "R89") (pin "P$1") (pinfunction "P$1_P$1") (pintype "passive"))
      (node (ref "R9") (pin "P$1") (pinfunction "P$1_P$1") (pintype "passive"))
      (node (ref "R93") (pin "P$1") (pinfunction "P$1_P$1") (pintype "passive"))
      (node (ref "U1") (pin "3") (pinfunction "GND_3") (pintype "bidirectional"))
      (node (ref "U10") (pin "P$2") (pinfunction "V-_P$2") (pintype "bidirectional"))
      (node (ref "U11") (pin "P$2") (pinfunction "V-_P$2") (pintype "bidirectional"))
      (node (ref "U12") (pin "P$2") (pinfunction "V-_P$2") (pintype "bidirectional"))
      (node (ref "U13") (pin "P$2") (pinfunction "GND_P$2") (pintype "bidirectional"))
      (node (ref "U13") (pin "P$4") (pinfunction "GND_P$4") (pintype "bidirectional"))
      (node (ref "U14") (pin "2") (pinfunction "VSS_2") (pintype "bidirectional"))
      (node (ref "U15") (pin "9") (pinfunction "VSS_9") (pintype "power_in"))
      (node (ref "U2") (pin "3") (pinfunction "GND_3") (pintype "bidirectional"))
      (node (ref "U3") (pin "3") (pinfunction "GND_3") (pintype "bidirectional"))
      (node (ref "U4") (pin "3") (pinfunction "GND_3") (pintype "bidirectional"))
      (node (ref "U5") (pin "P$2") (pinfunction "V-_P$2") (pintype "bidirectional"))
      (node (ref "U6") (pin "P$2") (pinfunction "V-_P$2") (pintype "bidirectional"))
      (node (ref "U7") (pin "P$2") (pinfunction "V-_P$2") (pintype "bidirectional"))
      (node (ref "U8") (pin "P$2") (pinfunction "V-_P$2") (pintype "bidirectional"))
      (node (ref "U9") (pin "P$2") (pinfunction "V-_P$2") (pintype "bidirectional"))
      (node (ref "XIO") (pin "35") (pinfunction "35_35") (pintype "passive"))
      (node (ref "XIO") (pin "36") (pinfunction "36_36") (pintype "passive"))
    )
    (net (code "15") (name "INT") (class "Default")
      (node (ref "COMMUNICATION") (pin "1") (pinfunction "1_1") (pintype "passive"))
      (node (ref "D21") (pin "CATHODE") (pinfunction "CATHODE_CATHODE") (pintype "power_in"))
      (node (ref "U15") (pin "12") (pinfunction "~{INT}_12") (pintype "output"))
    )
    (net (code "16") (name "MISO") (class "Default")
      (node (ref "U15") (pin "15") (pinfunction "SO_15") (pintype "output"))
      (node (ref "XIO") (pin "31") (pinfunction "31_31") (pintype "passive"))
    )
    (net (code "17") (name "MOSI") (class "Default")
      (node (ref "U15") (pin "14") (pinfunction "SI_14") (pintype "input"))
      (node (ref "XIO") (pin "32") (pinfunction "32_32") (pintype "passive"))
    )
    (net (code "18") (name "MTT") (class "Default")
      (node (ref "ADCH") (pin "1") (pinfunction "1_1") (pintype "passive"))
      (node (ref "R116") (pin "P$1") (pinfunction "P$1_P$1") (pintype "passive"))
      (node (ref "R118") (pin "P$2") (pinfunction "P$2_P$2") (pintype "passive"))
    )
    (net (code "19") (name "Net-(C1-PadP$1)") (class "Default")
      (node (ref "C1") (pin "P$1") (pinfunction "P$1_P$1") (pintype "passive"))
      (node (ref "CON3") (pin "P$1") (pinfunction "P$1_P$1") (pintype "bidirectional"))
      (node (ref "D3") (pin "CATHODE") (pinfunction "CATHODE_CATHODE") (pintype "bidirectional"))
      (node (ref "L3") (pin "P$2") (pinfunction "P$2_P$2") (pintype "passive"))
    )
    (net (code "20") (name "Net-(C2-PadP$1)") (class "Default")
      (node (ref "C2") (pin "P$1") (pinfunction "P$1_P$1") (pintype "passive"))
      (node (ref "CON4") (pin "P$1") (pinfunction "P$1_P$1") (pintype "bidirectional"))
      (node (ref "D4") (pin "CATHODE") (pinfunction "CATHODE_CATHODE") (pintype "bidirectional"))
      (node (ref "L4") (pin "P$2") (pinfunction "P$2_P$2") (pintype "passive"))
    )
    (net (code "21") (name "Net-(C3-PadP$1)") (class "Default")
      (node (ref "C3") (pin "P$1") (pinfunction "P$1_P$1") (pintype "passive"))
      (node (ref "R3") (pin "P$2") (pinfunction "P$2_P$2") (pintype "passive"))
    )
    (net (code "22") (name "Net-(C4-PadP$1)") (class "Default")
      (node (ref "C4") (pin "P$1") (pinfunction "P$1_P$1") (pintype "passive"))
      (node (ref "R4") (pin "P$2") (pinfunction "P$2_P$2") (pintype "passive"))
    )
    (net (code "23") (name "Net-(C7-PadP$1)") (class "Default")
      (node (ref "C7") (pin "P$1") (pinfunction "P$1_P$1") (pintype "passive"))
      (node (ref "R5") (pin "P$2") (pinfunction "P$2_P$2") (pintype "passive"))
    )
    (net (code "24") (name "Net-(C8-PadP$1)") (class "Default")
      (node (ref "C8") (pin "P$1") (pinfunction "P$1_P$1") (pintype "passive"))
      (node (ref "R6") (pin "P$2") (pinfunction "P$2_P$2") (pintype "passive"))
    )
    (net (code "25") (name "Net-(C9-PadP$1)") (class "Default")
      (node (ref "C9") (pin "P$1") (pinfunction "P$1_P$1") (pintype "passive"))
      (node (ref "CON1") (pin "P$1") (pinfunction "P$1_P$1") (pintype "bidirectional"))
      (node (ref "D1") (pin "CATHODE") (pinfunction "CATHODE_CATHODE") (pintype "bidirectional"))
      (node (ref "L1") (pin "P$2") (pinfunction "P$2_P$2") (pintype "passive"))
    )
    (net (code "26") (name "Net-(C10-PadP$1)") (class "Default")
      (node (ref "C10") (pin "P$1") (pinfunction "P$1_P$1") (pintype "passive"))
      (node (ref "CON2") (pin "P$1") (pinfunction "P$1_P$1") (pintype "bidirectional"))
      (node (ref "D2") (pin "CATHODE") (pinfunction "CATHODE_CATHODE") (pintype "bidirectional"))
      (node (ref "L2") (pin "P$2") (pinfunction "P$2_P$2") (pintype "passive"))
    )
    (net (code "27") (name "Net-(C13-PadP$1)") (class "Default")
      (node (ref "C13") (pin "P$1") (pinfunction "P$1_P$1") (pintype "passive"))
      (node (ref "CON5") (pin "P$1") (pinfunction "P$1_P$1") (pintype "bidirectional"))
      (node (ref "D5") (pin "CATHODE") (pinfunction "CATHODE_CATHODE") (pintype "bidirectional"))
      (node (ref "L5") (pin "P$2") (pinfunction "P$2_P$2") (pintype "passive"))
    )
    (net (code "28") (name "Net-(C14-PadP$1)") (class "Default")
      (node (ref "C14") (pin "P$1") (pinfunction "P$1_P$1") (pintype "passive"))
      (node (ref "CON6") (pin "P$1") (pinfunction "P$1_P$1") (pintype "bidirectional"))
      (node (ref "D6") (pin "CATHODE") (pinfunction "CATHODE_CATHODE") (pintype "bidirectional"))
      (node (ref "L6") (pin "P$2") (pinfunction "P$2_P$2") (pintype "passive"))
    )
    (net (code "29") (name "Net-(C15-PadP$1)") (class "Default")
      (node (ref "C15") (pin "P$1") (pinfunction "P$1_P$1") (pintype "passive"))
      (node (ref "CON7") (pin "P$1") (pinfunction "P$1_P$1") (pintype "bidirectional"))
      (node (ref "D7") (pin "CATHODE") (pinfunction "CATHODE_CATHODE") (pintype "bidirectional"))
      (node (ref "L7") (pin "P$2") (pinfunction "P$2_P$2") (pintype "passive"))
    )
    (net (code "30") (name "Net-(C16-PadP$1)") (class "Default")
      (node (ref "C16") (pin "P$1") (pinfunction "P$1_P$1") (pintype "passive"))
      (node (ref "CON8") (pin "P$1") (pinfunction "P$1_P$1") (pintype "bidirectional"))
      (node (ref "D8") (pin "CATHODE") (pinfunction "CATHODE_CATHODE") (pintype "bidirectional"))
      (node (ref "L8") (pin "P$2") (pinfunction "P$2_P$2") (pintype "passive"))
    )
    (net (code "31") (name "Net-(C19-PadP$1)") (class "Default")
      (node (ref "C19") (pin "P$1") (pinfunction "P$1_P$1") (pintype "passive"))
      (node (ref "R21") (pin "P$2") (pinfunction "P$2_P$2") (pintype "passive"))
    )
    (net (code "32") (name "Net-(C20-PadP$1)") (class "Default")
      (node (ref "C20") (pin "P$1") (pinfunction "P$1_P$1") (pintype "passive"))
      (node (ref "R22") (pin "P$2") (pinfunction "P$2_P$2") (pintype "passive"))
    )
    (net (code "33") (name "Net-(C21-PadP$1)") (class "Default")
      (node (ref "C21") (pin "P$1") (pinfunction "P$1_P$1") (pintype "passive"))
      (node (ref "R23") (pin "P$2") (pinfunction "P$2_P$2") (pintype "passive"))
    )
    (net (code "34") (name "Net-(C22-PadP$1)") (class "Default")
      (node (ref "C22") (pin "P$1") (pinfunction "P$1_P$1") (pintype "passive"))
      (node (ref "R24") (pin "P$2") (pinfunction "P$2_P$2") (pintype "passive"))
    )
    (net (code "35") (name "Net-(C25-PadP$1)") (class "Default")
      (node (ref "C25") (pin "P$1") (pinfunction "P$1_P$1") (pintype "passive"))
      (node (ref "R36") (pin "P$2") (pinfunction "P$2_P$2") (pintype "passive"))
      (node (ref "R51") (pin "P$1") (pinfunction "P$1_P$1") (pintype "passive"))
    )
    (net (code "36") (name "Net-(C25-PadP$2)") (class "Default")
      (node (ref "C25") (pin "P$2") (pinfunction "P$2_P$2") (pintype "passive"))
      (node (ref "R37") (pin "P$2") (pinfunction "P$2_P$2") (pintype "passive"))
      (node (ref "R52") (pin "P$1") (pinfunction "P$1_P$1") (pintype "passive"))
    )
    (net (code "37") (name "Net-(C28-PadP$1)") (class "Default")
      (node (ref "C28") (pin "P$1") (pinfunction "P$1_P$1") (pintype "passive"))
      (node (ref "R38") (pin "P$2") (pinfunction "P$2_P$2") (pintype "passive"))
      (node (ref "R53") (pin "P$1") (pinfunction "P$1_P$1") (pintype "passive"))
    )
    (net (code "38") (name "Net-(C28-PadP$2)") (class "Default")
      (node (ref "C28") (pin "P$2") (pinfunction "P$2_P$2") (pintype "passive"))
      (node (ref "R39") (pin "P$2") (pinfunction "P$2_P$2") (pintype "passive"))
      (node (ref "R54") (pin "P$1") (pinfunction "P$1_P$1") (pintype "passive"))
    )
    (net (code "39") (name "Net-(C31-PadP$1)") (class "Default")
      (node (ref "C31") (pin "P$1") (pinfunction "P$1_P$1") (pintype "passive"))
      (node (ref "R40") (pin "P$2") (pinfunction "P$2_P$2") (pintype "passive"))
      (node (ref "R55") (pin "P$1") (pinfunction "P$1_P$1") (pintype "passive"))
    )
    (net (code "40") (name "Net-(C31-PadP$2)") (class "Default")
      (node (ref "C31") (pin "P$2") (pinfunction "P$2_P$2") (pintype "passive"))
      (node (ref "R41") (pin "P$2") (pinfunction "P$2_P$2") (pintype "passive"))
      (node (ref "R56") (pin "P$1") (pinfunction "P$1_P$1") (pintype "passive"))
    )
    (net (code "41") (name "Net-(C34-PadP$1)") (class "Default")
      (node (ref "C34") (pin "P$1") (pinfunction "P$1_P$1") (pintype "passive"))
      (node (ref "R58") (pin "P$2") (pinfunction "P$2_P$2") (pintype "passive"))
      (node (ref "R63") (pin "P$1") (pinfunction "P$1_P$1") (pintype "passive"))
    )
    (net (code "42") (name "Net-(C34-PadP$2)") (class "Default")
      (node (ref "C34") (pin "P$2") (pinfunction "P$2_P$2") (pintype "passive"))
      (node (ref "R59") (pin "P$2") (pinfunction "P$2_P$2") (pintype "passive"))
      (node (ref "R64") (pin "P$1") (pinfunction "P$1_P$1") (pintype "passive"))
    )
    (net (code "43") (name "Net-(C37-PadP$1)") (class "Default")
      (node (ref "C37") (pin "P$1") (pinfunction "P$1_P$1") (pintype "passive"))
      (node (ref "R68") (pin "P$2") (pinfunction "P$2_P$2") (pintype "passive"))
      (node (ref "R83") (pin "P$1") (pinfunction "P$1_P$1") (pintype "passive"))
    )
    (net (code "44") (name "Net-(C37-PadP$2)") (class "Default")
      (node (ref "C37") (pin "P$2") (pinfunction "P$2_P$2") (pintype "passive"))
      (node (ref "R69") (pin "P$2") (pinfunction "P$2_P$2") (pintype "passive"))
      (node (ref "R84") (pin "P$1") (pinfunction "P$1_P$1") (pintype "passive"))
    )
    (net (code "45") (name "Net-(C40-PadP$1)") (class "Default")
      (node (ref "C40") (pin "P$1") (pinfunction "P$1_P$1") (pintype "passive"))
      (node (ref "R70") (pin "P$2") (pinfunction "P$2_P$2") (pintype "passive"))
      (node (ref "R85") (pin "P$1") (pinfunction "P$1_P$1") (pintype "passive"))
    )
    (net (code "46") (name "Net-(C40-PadP$2)") (class "Default")
      (node (ref "C40") (pin "P$2") (pinfunction "P$2_P$2") (pintype "passive"))
      (node (ref "R71") (pin "P$2") (pinfunction "P$2_P$2") (pintype "passive"))
      (node (ref "R86") (pin "P$1") (pinfunction "P$1_P$1") (pintype "passive"))
    )
    (net (code "47") (name "Net-(C43-PadP$1)") (class "Default")
      (node (ref "C43") (pin "P$1") (pinfunction "P$1_P$1") (pintype "passive"))
      (node (ref "R72") (pin "P$2") (pinfunction "P$2_P$2") (pintype "passive"))
      (node (ref "R87") (pin "P$1") (pinfunction "P$1_P$1") (pintype "passive"))
    )
    (net (code "48") (name "Net-(C43-PadP$2)") (class "Default")
      (node (ref "C43") (pin "P$2") (pinfunction "P$2_P$2") (pintype "passive"))
      (node (ref "R73") (pin "P$2") (pinfunction "P$2_P$2") (pintype "passive"))
      (node (ref "R88") (pin "P$1") (pinfunction "P$1_P$1") (pintype "passive"))
    )
    (net (code "49") (name "Net-(C46-PadP$1)") (class "Default")
      (node (ref "C46") (pin "P$1") (pinfunction "P$1_P$1") (pintype "passive"))
      (node (ref "R90") (pin "P$2") (pinfunction "P$2_P$2") (pintype "passive"))
      (node (ref "R95") (pin "P$1") (pinfunction "P$1_P$1") (pintype "passive"))
    )
    (net (code "50") (name "Net-(C46-PadP$2)") (class "Default")
      (node (ref "C46") (pin "P$2") (pinfunction "P$2_P$2") (pintype "passive"))
      (node (ref "R91") (pin "P$2") (pinfunction "P$2_P$2") (pintype "passive"))
      (node (ref "R96") (pin "P$1") (pinfunction "P$1_P$1") (pintype "passive"))
    )
    (net (code "51") (name "Net-(C50-PadP$1)") (class "Default")
      (node (ref "C50") (pin "P$1") (pinfunction "P$1_P$1") (pintype "passive"))
      (node (ref "R101") (pin "P$2") (pinfunction "P$2_P$2") (pintype "passive"))
    )
    (net (code "52") (name "Net-(CON1-PadP$2)") (class "Default")
      (node (ref "CON1") (pin "P$2") (pinfunction "P$2_P$2") (pintype "bidirectional"))
      (node (ref "D1") (pin "ANODE") (pinfunction "ANODE_ANODE") (pintype "bidirectional"))
      (node (ref "Q1") (pin "P$5") (pinfunction "DRAIN_P$5") (pintype "bidirectional"))
      (node (ref "Q1") (pin "P$6") (pinfunction "DRAIN_P$6") (pintype "bidirectional"))
      (node (ref "Q1") (pin "P$7") (pinfunction "DRAIN_P$7") (pintype "bidirectional"))
      (node (ref "Q1") (pin "P$8") (pinfunction "DRAIN_P$8") (pintype "bidirectional"))
      (node (ref "Q1") (pin "P$9") (pinfunction "DRAIN_P$9") (pintype "bidirectional"))
      (node (ref "R3") (pin "P$1") (pinfunction "P$1_P$1") (pintype "passive"))
    )
    (net (code "53") (name "Net-(CON2-PadP$2)") (class "Default")
      (node (ref "CON2") (pin "P$2") (pinfunction "P$2_P$2") (pintype "bidirectional"))
      (node (ref "D2") (pin "ANODE") (pinfunction "ANODE_ANODE") (pintype "bidirectional"))
      (node (ref "Q2") (pin "P$5") (pinfunction "DRAIN_P$5") (pintype "bidirectional"))
      (node (ref "Q2") (pin "P$6") (pinfunction "DRAIN_P$6") (pintype "bidirectional"))
      (node (ref "Q2") (pin "P$7") (pinfunction "DRAIN_P$7") (pintype "bidirectional"))
      (node (ref "Q2") (pin "P$8") (pinfunction "DRAIN_P$8") (pintype "bidirectional"))
      (node (ref "Q2") (pin "P$9") (pinfunction "DRAIN_P$9") (pintype "bidirectional"))
      (node (ref "R4") (pin "P$1") (pinfunction "P$1_P$1") (pintype "passive"))
    )
    (net (code "54") (name "Net-(CON3-PadP$2)") (class "Default")
      (node (ref "CON3") (pin "P$2") (pinfunction "P$2_P$2") (pintype "bidirectional"))
      (node (ref "D3") (pin "ANODE") (pinfunction "ANODE_ANODE") (pintype "bidirectional"))
      (node (ref "Q3") (pin "P$5") (pinfunction "DRAIN_P$5") (pintype "bidirectional"))
      (node (ref "Q3") (pin "P$6") (pinfunction "DRAIN_P$6") (pintype "bidirectional"))
      (node (ref "Q3") (pin "P$7") (pinfunction "DRAIN_P$7") (pintype "bidirectional"))
      (node (ref "Q3") (pin "P$8") (pinfunction "DRAIN_P$8") (pintype "bidirectional"))
      (node (ref "Q3") (pin "P$9") (pinfunction "DRAIN_P$9") (pintype "bidirectional"))
      (node (ref "R5") (pin "P$1") (pinfunction "P$1_P$1") (pintype "passive"))
    )
    (net (code "55") (name "Net-(CON4-PadP$2)") (class "Default")
      (node (ref "CON4") (pin "P$2") (pinfunction "P$2_P$2") (pintype "bidirectional"))
      (node (ref "D4") (pin "ANODE") (pinfunction "ANODE_ANODE") (pintype "bidirectional"))
      (node (ref "Q4") (pin "P$5") (pinfunction "DRAIN_P$5") (pintype "bidirectional"))
      (node (ref "Q4") (pin "P$6") (pinfunction "DRAIN_P$6") (pintype "bidirectional"))
      (node (ref "Q4") (pin "P$7") (pinfunction "DRAIN_P$7") (pintype "bidirectional"))
      (node (ref "Q4") (pin "P$8") (pinfunction "DRAIN_P$8") (pintype "bidirectional"))
      (node (ref "Q4") (pin "P$9") (pinfunction "DRAIN_P$9") (pintype "bidirectional"))
      (node (ref "R6") (pin "P$1") (pinfunction "P$1_P$1") (pintype "passive"))
    )
    (net (code "56") (name "Net-(CON5-PadP$2)") (class "Default")
      (node (ref "CON5") (pin "P$2") (pinfunction "P$2_P$2") (pintype "bidirectional"))
      (node (ref "D5") (pin "ANODE") (pinfunction "ANODE_ANODE") (pintype "bidirectional"))
      (node (ref "Q5") (pin "P$5") (pinfunction "DRAIN_P$5") (pintype "bidirectional"))
      (node (ref "Q5") (pin "P$6") (pinfunction "DRAIN_P$6") (pintype "bidirectional"))
      (node (ref "Q5") (pin "P$7") (pinfunction "DRAIN_P$7") (pintype "bidirectional"))
      (node (ref "Q5") (pin "P$8") (pinfunction "DRAIN_P$8") (pintype "bidirectional"))
      (node (ref "Q5") (pin "P$9") (pinfunction "DRAIN_P$9") (pintype "bidirectional"))
      (node (ref "R21") (pin "P$1") (pinfunction "P$1_P$1") (pintype "passive"))
    )
    (net (code "57") (name "Net-(CON6-PadP$2)") (class "Default")
      (node (ref "CON6") (pin "P$2") (pinfunction "P$2_P$2") (pintype "bidirectional"))
      (node (ref "D6") (pin "ANODE") (pinfunction "ANODE_ANODE") (pintype "bidirectional"))
      (node (ref "Q6") (pin "P$5") (pinfunction "DRAIN_P$5") (pintype "bidirectional"))
      (node (ref "Q6") (pin "P$6") (pinfunction "DRAIN_P$6") (pintype "bidirectional"))
      (node (ref "Q6") (pin "P$7") (pinfunction "DRAIN_P$7") (pintype "bidirectional"))
      (node (ref "Q6") (pin "P$8") (pinfunction "DRAIN_P$8") (pintype "bidirectional"))
      (node (ref "Q6") (pin "P$9") (pinfunction "DRAIN_P$9") (pintype "bidirectional"))
      (node (ref "R22") (pin "P$1") (pinfunction "P$1_P$1") (pintype "passive"))
    )
    (net (code "58") (name "Net-(CON7-PadP$2)") (class "Default")
      (node (ref "CON7") (pin "P$2") (pinfunction "P$2_P$2") (pintype "bidirectional"))
      (node (ref "D7") (pin "ANODE") (pinfunction "ANODE_ANODE") (pintype "bidirectional"))
      (node (ref "Q7") (pin "P$5") (pinfunction "DRAIN_P$5") (pintype "bidirectional"))
      (node (ref "Q7") (pin "P$6") (pinfunction "DRAIN_P$6") (pintype "bidirectional"))
      (node (ref "Q7") (pin "P$7") (pinfunction "DRAIN_P$7") (pintype "bidirectional"))
      (node (ref "Q7") (pin "P$8") (pinfunction "DRAIN_P$8") (pintype "bidirectional"))
      (node (ref "Q7") (pin "P$9") (pinfunction "DRAIN_P$9") (pintype "bidirectional"))
      (node (ref "R23") (pin "P$1") (pinfunction "P$1_P$1") (pintype "passive"))
    )
    (net (code "59") (name "Net-(CON8-PadP$2)") (class "Default")
      (node (ref "CON8") (pin "P$2") (pinfunction "P$2_P$2") (pintype "bidirectional"))
      (node (ref "D8") (pin "ANODE") (pinfunction "ANODE_ANODE") (pintype "bidirectional"))
      (node (ref "Q8") (pin "P$5") (pinfunction "DRAIN_P$5") (pintype "bidirectional"))
      (node (ref "Q8") (pin "P$6") (pinfunction "DRAIN_P$6") (pintype "bidirectional"))
      (node (ref "Q8") (pin "P$7") (pinfunction "DRAIN_P$7") (pintype "bidirectional"))
      (node (ref "Q8") (pin "P$8") (pinfunction "DRAIN_P$8") (pintype "bidirectional"))
      (node (ref "Q8") (pin "P$9") (pinfunction "DRAIN_P$9") (pintype "bidirectional"))
      (node (ref "R24") (pin "P$1") (pinfunction "P$1_P$1") (pintype "passive"))
    )
    (net (code "60") (name "Net-(CON13-PadP$1)") (class "Default")
      (node (ref "CON13") (pin "P$1") (pinfunction "P$1_P$1") (pintype "bidirectional"))
      (node (ref "R119") (pin "P$1") (pinfunction "P$1_P$1") (pintype "passive"))
    )
    (net (code "61") (name "Net-(CON13-PadP$2)") (class "Default")
      (node (ref "CON13") (pin "P$2") (pinfunction "P$2_P$2") (pintype "bidirectional"))
      (node (ref "R117") (pin "P$1") (pinfunction "P$1_P$1") (pintype "passive"))
    )
    (net (code "62") (name "Net-(CON13-PadP$3)") (class "Default")
      (node (ref "CON13") (pin "P$3") (pinfunction "P$3_P$3") (pintype "bidirectional"))
      (node (ref "R118") (pin "P$1") (pinfunction "P$1_P$1") (pintype "passive"))
    )
    (net (code "63") (name "Net-(CON15-PadP$1)") (class "Default")
      (node (ref "CON15") (pin "P$1") (pinfunction "P$1_P$1") (pintype "bidirectional"))
      (node (ref "R106") (pin "P$2") (pinfunction "P$2_P$2") (pintype "passive"))
    )
    (net (code "64") (name "Net-(CON15-PadP$2)") (class "Default")
      (node (ref "CON15") (pin "P$2") (pinfunction "P$2_P$2") (pintype "bidirectional"))
      (node (ref "R107") (pin "P$2") (pinfunction "P$2_P$2") (pintype "passive"))
    )
    (net (code "65") (name "Net-(CON15-PadP$3)") (class "Default")
      (node (ref "CON15") (pin "P$3") (pinfunction "P$3_P$3") (pintype "bidirectional"))
      (node (ref "R108") (pin "P$2") (pinfunction "P$2_P$2") (pintype "passive"))
    )
    (net (code "66") (name "Net-(CON15-PadP$4)") (class "Default")
      (node (ref "CON15") (pin "P$4") (pinfunction "P$4_P$4") (pintype "bidirectional"))
      (node (ref "R109") (pin "P$2") (pinfunction "P$2_P$2") (pintype "passive"))
    )
    (net (code "67") (name "Net-(CON15-PadP$5)") (class "Default")
      (node (ref "CON15") (pin "P$5") (pinfunction "P$5_P$5") (pintype "bidirectional"))
      (node (ref "R110") (pin "P$2") (pinfunction "P$2_P$2") (pintype "passive"))
    )
    (net (code "68") (name "Net-(D9-PadCATHODE)") (class "Default")
      (node (ref "D9") (pin "CATHODE") (pinfunction "CATHODE_CATHODE") (pintype "bidirectional"))
      (node (ref "R60") (pin "P$1") (pinfunction "P$1_P$1") (pintype "passive"))
    )
    (net (code "69") (name "Net-(D10-PadCATHODE)") (class "Default")
      (node (ref "D10") (pin "CATHODE") (pinfunction "CATHODE_CATHODE") (pintype "bidirectional"))
      (node (ref "R42") (pin "P$1") (pinfunction "P$1_P$1") (pintype "passive"))
    )
    (net (code "70") (name "Net-(D11-PadCATHODE)") (class "Default")
      (node (ref "D11") (pin "CATHODE") (pinfunction "CATHODE_CATHODE") (pintype "bidirectional"))
      (node (ref "R43") (pin "P$1") (pinfunction "P$1_P$1") (pintype "passive"))
    )
    (net (code "71") (name "Net-(D12-PadCATHODE)") (class "Default")
      (node (ref "D12") (pin "CATHODE") (pinfunction "CATHODE_CATHODE") (pintype "bidirectional"))
      (node (ref "R44") (pin "P$1") (pinfunction "P$1_P$1") (pintype "passive"))
    )
    (net (code "72") (name "Net-(D13-PadCATHODE)") (class "Default")
      (node (ref "D13") (pin "CATHODE") (pinfunction "CATHODE_CATHODE") (pintype "bidirectional"))
      (node (ref "R92") (pin "P$1") (pinfunction "P$1_P$1") (pintype "passive"))
    )
    (net (code "73") (name "Net-(D14-PadCATHODE)") (class "Default")
      (node (ref "D14") (pin "CATHODE") (pinfunction "CATHODE_CATHODE") (pintype "bidirectional"))
      (node (ref "R74") (pin "P$1") (pinfunction "P$1_P$1") (pintype "passive"))
    )
    (net (code "74") (name "Net-(D15-PadCATHODE)") (class "Default")
      (node (ref "D15") (pin "CATHODE") (pinfunction "CATHODE_CATHODE") (pintype "bidirectional"))
      (node (ref "R75") (pin "P$1") (pinfunction "P$1_P$1") (pintype "passive"))
    )
    (net (code "75") (name "Net-(D16-PadCATHODE)") (class "Default")
      (node (ref "D16") (pin "CATHODE") (pinfunction "CATHODE_CATHODE") (pintype "bidirectional"))
      (node (ref "R76") (pin "P$1") (pinfunction "P$1_P$1") (pintype "passive"))
    )
    (net (code "76") (name "Net-(D17-PadANODE)") (class "Default")
      (node (ref "D17") (pin "ANODE") (pinfunction "ANODE_ANODE") (pintype "power_in"))
      (node (ref "R103") (pin "P$1") (pinfunction "P$1_P$1") (pintype "passive"))
    )
    (net (code "77") (name "Net-(D18-PadANODE)") (class "Default")
      (node (ref "D18") (pin "ANODE") (pinfunction "ANODE_ANODE") (pintype "power_in"))
      (node (ref "R97") (pin "P$1") (pinfunction "P$1_P$1") (pintype "passive"))
    )
    (net (code "78") (name "Net-(D19-PadANODE)") (class "Default")
      (node (ref "D19") (pin "ANODE") (pinfunction "ANODE_ANODE") (pintype "power_in"))
      (node (ref "R98") (pin "P$1") (pinfunction "P$1_P$1") (pintype "passive"))
    )
    (net (code "79") (name "Net-(D20-PadANODE)") (class "Default")
      (node (ref "D20") (pin "ANODE") (pinfunction "ANODE_ANODE") (pintype "power_in"))
      (node (ref "R99") (pin "P$1") (pinfunction "P$1_P$1") (pintype "passive"))
    )
    (net (code "80") (name "Net-(D21-PadANODE)") (class "Default")
      (node (ref "D21") (pin "ANODE") (pinfunction "ANODE_ANODE") (pintype "power_in"))
      (node (ref "R100") (pin "P$1") (pinfunction "P$1_P$1") (pintype "passive"))
    )
    (net (code "81") (name "Net-(F3-P$1-PadP$2)") (class "Default")
      (node (ref "F3") (pin "P$1") (pinfunction "P$1_P$1") (pintype "bidirectional"))
      (node (ref "F3") (pin "P$2") (pinfunction "P$1_P$2") (pintype "bidirectional"))
      (node (ref "F3") (pin "P$3") (pinfunction "P$1_P$3") (pintype "bidirectional"))
      (node (ref "F3") (pin "P$4") (pinfunction "P$1_P$4") (pintype "bidirectional"))
      (node (ref "RELAY3") (pin "30") (pinfunction "30_30") (pintype "bidirectional"))
    )
    (net (code "82") (name "Net-(JP2-Pad2)") (class "Default")
      (node (ref "JP2") (pin "2") (pinfunction "2_2") (pintype "passive"))
      (node (ref "R102") (pin "P$2") (pinfunction "P$2_P$2") (pintype "passive"))
    )
    (net (code "83") (name "Net-(Q9-DRAIN)") (class "Default")
      (node (ref "Q9") (pin "P$3") (pinfunction "DRAIN_P$3") (pintype "bidirectional"))
      (node (ref "RELAY3") (pin "85") (pinfunction "85_85") (pintype "bidirectional"))
    )
    (net (code "84") (name "Net-(Q10-D)") (class "Default")
      (node (ref "D17") (pin "CATHODE") (pinfunction "CATHODE_CATHODE") (pintype "power_in"))
      (node (ref "Q10") (pin "P$3") (pinfunction "D_P$3") (pintype "passive"))
      (node (ref "RELAY1") (pin "P$12") (pinfunction "P$12_P$12") (pintype "bidirectional"))
    )
    (net (code "85") (name "Net-(Q11-DRAIN)") (class "Default")
      (node (ref "Q11") (pin "P$3") (pinfunction "DRAIN_P$3") (pintype "bidirectional"))
      (node (ref "R117") (pin "P$2") (pinfunction "P$2_P$2") (pintype "passive"))
    )
    (net (code "86") (name "Net-(Q12-DRAIN)") (class "Default")
      (node (ref "Q12") (pin "P$3") (pinfunction "DRAIN_P$3") (pintype "bidirectional"))
      (node (ref "R119") (pin "P$2") (pinfunction "P$2_P$2") (pintype "passive"))
    )
    (net (code "87") (name "Net-(U5-IN+)") (class "Default")
      (node (ref "R61") (pin "P$2") (pinfunction "P$2_P$2") (pintype "passive"))
      (node (ref "R64") (pin "P$2") (pinfunction "P$2_P$2") (pintype "passive"))
      (node (ref "U5") (pin "P$3") (pinfunction "IN+_P$3") (pintype "bidirectional"))
    )
    (net (code "88") (name "Net-(U5-IN-)") (class "Default")
      (node (ref "R62") (pin "P$2") (pinfunction "P$2_P$2") (pintype "passive"))
      (node (ref "R63") (pin "P$2") (pinfunction "P$2_P$2") (pintype "passive"))
      (node (ref "U5") (pin "P$4") (pinfunction "IN-_P$4") (pintype "bidirectional"))
    )
    (net (code "89") (name "Net-(U5-OUT)") (class "Default")
      (node (ref "D9") (pin "ANODE") (pinfunction "ANODE_ANODE") (pintype "bidirectional"))
      (node (ref "R62") (pin "P$1") (pinfunction "P$1_P$1") (pintype "passive"))
      (node (ref "U5") (pin "P$1") (pinfunction "OUT_P$1") (pintype "bidirectional"))
    )
    (net (code "90") (name "Net-(U6-IN+)") (class "Default")
      (node (ref "R45") (pin "P$2") (pinfunction "P$2_P$2") (pintype "passive"))
      (node (ref "R52") (pin "P$2") (pinfunction "P$2_P$2") (pintype "passive"))
      (node (ref "U6") (pin "P$3") (pinfunction "IN+_P$3") (pintype "bidirectional"))
    )
    (net (code "91") (name "Net-(U6-IN-)") (class "Default")
      (node (ref "R48") (pin "P$2") (pinfunction "P$2_P$2") (pintype "passive"))
      (node (ref "R51") (pin "P$2") (pinfunction "P$2_P$2") (pintype "passive"))
      (node (ref "U6") (pin "P$4") (pinfunction "IN-_P$4") (pintype "bidirectional"))
    )
    (net (code "92") (name "Net-(U6-OUT)") (class "Default")
      (node (ref "D10") (pin "ANODE") (pinfunction "ANODE_ANODE") (pintype "bidirectional"))
      (node (ref "R48") (pin "P$1") (pinfunction "P$1_P$1") (pintype "passive"))
      (node (ref "U6") (pin "P$1") (pinfunction "OUT_P$1") (pintype "bidirectional"))
    )
    (net (code "93") (name "Net-(U7-IN+)") (class "Default")
      (node (ref "R46") (pin "P$2") (pinfunction "P$2_P$2") (pintype "passive"))
      (node (ref "R54") (pin "P$2") (pinfunction "P$2_P$2") (pintype "passive"))
      (node (ref "U7") (pin "P$3") (pinfunction "IN+_P$3") (pintype "bidirectional"))
    )
    (net (code "94") (name "Net-(U7-IN-)") (class "Default")
      (node (ref "R49") (pin "P$2") (pinfunction "P$2_P$2") (pintype "passive"))
      (node (ref "R53") (pin "P$2") (pinfunction "P$2_P$2") (pintype "passive"))
      (node (ref "U7") (pin "P$4") (pinfunction "IN-_P$4") (pintype "bidirectional"))
    )
    (net (code "95") (name "Net-(U7-OUT)") (class "Default")
      (node (ref "D11") (pin "ANODE") (pinfunction "ANODE_ANODE") (pintype "bidirectional"))
      (node (ref "R49") (pin "P$1") (pinfunction "P$1_P$1") (pintype "passive"))
      (node (ref "U7") (pin "P$1") (pinfunction "OUT_P$1") (pintype "bidirectional"))
    )
    (net (code "96") (name "Net-(U8-IN+)") (class "Default")
      (node (ref "R47") (pin "P$2") (pinfunction "P$2_P$2") (pintype "passive"))
      (node (ref "R56") (pin "P$2") (pinfunction "P$2_P$2") (pintype "passive"))
      (node (ref "U8") (pin "P$3") (pinfunction "IN+_P$3") (pintype "bidirectional"))
    )
    (net (code "97") (name "Net-(U8-IN-)") (class "Default")
      (node (ref "R50") (pin "P$2") (pinfunction "P$2_P$2") (pintype "passive"))
      (node (ref "R55") (pin "P$2") (pinfunction "P$2_P$2") (pintype "passive"))
      (node (ref "U8") (pin "P$4") (pinfunction "IN-_P$4") (pintype "bidirectional"))
    )
    (net (code "98") (name "Net-(U8-OUT)") (class "Default")
      (node (ref "D12") (pin "ANODE") (pinfunction "ANODE_ANODE") (pintype "bidirectional"))
      (node (ref "R50") (pin "P$1") (pinfunction "P$1_P$1") (pintype "passive"))
      (node (ref "U8") (pin "P$1") (pinfunction "OUT_P$1") (pintype "bidirectional"))
    )
    (net (code "99") (name "Net-(U9-IN+)") (class "Default")
      (node (ref "R93") (pin "P$2") (pinfunction "P$2_P$2") (pintype "passive"))
      (node (ref "R96") (pin "P$2") (pinfunction "P$2_P$2") (pintype "passive"))
      (node (ref "U9") (pin "P$3") (pinfunction "IN+_P$3") (pintype "bidirectional"))
    )
    (net (code "100") (name "Net-(U9-IN-)") (class "Default")
      (node (ref "R94") (pin "P$2") (pinfunction "P$2_P$2") (pintype "passive"))
      (node (ref "R95") (pin "P$2") (pinfunction "P$2_P$2") (pintype "passive"))
      (node (ref "U9") (pin "P$4") (pinfunction "IN-_P$4") (pintype "bidirectional"))
    )
    (net (code "101") (name "Net-(U9-OUT)") (class "Default")
      (node (ref "D13") (pin "ANODE") (pinfunction "ANODE_ANODE") (pintype "bidirectional"))
      (node (ref "R94") (pin "P$1") (pinfunction "P$1_P$1") (pintype "passive"))
      (node (ref "U9") (pin "P$1") (pinfunction "OUT_P$1") (pintype "bidirectional"))
    )
    (net (code "102") (name "Net-(U10-IN+)") (class "Default")
      (node (ref "R77") (pin "P$2") (pinfunction "P$2_P$2") (pintype "passive"))
      (node (ref "R84") (pin "P$2") (pinfunction "P$2_P$2") (pintype "passive"))
      (node (ref "U10") (pin "P$3") (pinfunction "IN+_P$3") (pintype "bidirectional"))
    )
    (net (code "103") (name "Net-(U10-IN-)") (class "Default")
      (node (ref "R80") (pin "P$2") (pinfunction "P$2_P$2") (pintype "passive"))
      (node (ref "R83") (pin "P$2") (pinfunction "P$2_P$2") (pintype "passive"))
      (node (ref "U10") (pin "P$4") (pinfunction "IN-_P$4") (pintype "bidirectional"))
    )
    (net (code "104") (name "Net-(U10-OUT)") (class "Default")
      (node (ref "D14") (pin "ANODE") (pinfunction "ANODE_ANODE") (pintype "bidirectional"))
      (node (ref "R80") (pin "P$1") (pinfunction "P$1_P$1") (pintype "passive"))
      (node (ref "U10") (pin "P$1") (pinfunction "OUT_P$1") (pintype "bidirectional"))
    )
    (net (code "105") (name "Net-(U11-IN+)") (class "Default")
      (node (ref "R78") (pin "P$2") (pinfunction "P$2_P$2") (pintype "passive"))
      (node (ref "R86") (pin "P$2") (pinfunction "P$2_P$2") (pintype "passive"))
      (node (ref "U11") (pin "P$3") (pinfunction "IN+_P$3") (pintype "bidirectional"))
    )
    (net (code "106") (name "Net-(U11-IN-)") (class "Default")
      (node (ref "R81") (pin "P$2") (pinfunction "P$2_P$2") (pintype "passive"))
      (node (ref "R85") (pin "P$2") (pinfunction "P$2_P$2") (pintype "passive"))
      (node (ref "U11") (pin "P$4") (pinfunction "IN-_P$4") (pintype "bidirectional"))
    )
    (net (code "107") (name "Net-(U11-OUT)") (class "Default")
      (node (ref "D15") (pin "ANODE") (pinfunction "ANODE_ANODE") (pintype "bidirectional"))
      (node (ref "R81") (pin "P$1") (pinfunction "P$1_P$1") (pintype "passive"))
      (node (ref "U11") (pin "P$1") (pinfunction "OUT_P$1") (pintype "bidirectional"))
    )
    (net (code "108") (name "Net-(U12-IN+)") (class "Default")
      (node (ref "R79") (pin "P$2") (pinfunction "P$2_P$2") (pintype "passive"))
      (node (ref "R88") (pin "P$2") (pinfunction "P$2_P$2") (pintype "passive"))
      (node (ref "U12") (pin "P$3") (pinfunction "IN+_P$3") (pintype "bidirectional"))
    )
    (net (code "109") (name "Net-(U12-IN-)") (class "Default")
      (node (ref "R82") (pin "P$2") (pinfunction "P$2_P$2") (pintype "passive"))
      (node (ref "R87") (pin "P$2") (pinfunction "P$2_P$2") (pintype "passive"))
      (node (ref "U12") (pin "P$4") (pinfunction "IN-_P$4") (pintype "bidirectional"))
    )
    (net (code "110") (name "Net-(U12-OUT)") (class "Default")
      (node (ref "D16") (pin "ANODE") (pinfunction "ANODE_ANODE") (pintype "bidirectional"))
      (node (ref "R82") (pin "P$1") (pinfunction "P$1_P$1") (pintype "passive"))
      (node (ref "U12") (pin "P$1") (pinfunction "OUT_P$1") (pintype "bidirectional"))
    )
    (net (code "111") (name "Net-(U14-RS)") (class "Default")
      (node (ref "R105") (pin "P$1") (pinfunction "P$1_P$1") (pintype "passive"))
      (node (ref "U14") (pin "8") (pinfunction "RS_8") (pintype "bidirectional"))
    )
    (net (code "112") (name "Net-(U15-OSC1)") (class "Default")
      (node (ref "C53") (pin "P$2") (pinfunction "P$2_P$2") (pintype "passive"))
      (node (ref "U15") (pin "8") (pinfunction "OSC1_8") (pintype "input"))
      (node (ref "X1") (pin "1") (pinfunction "1_1") (pintype "passive"))
    )
    (net (code "113") (name "Net-(U15-OSC2)") (class "Default")
      (node (ref "C52") (pin "P$2") (pinfunction "P$2_P$2") (pintype "passive"))
      (node (ref "U15") (pin "7") (pinfunction "OSC2_7") (pintype "output"))
      (node (ref "X1") (pin "2") (pinfunction "2_2") (pintype "passive"))
    )
    (net (code "114") (name "Net-(U15-~{RESET})") (class "Default")
      (node (ref "R104") (pin "P$2") (pinfunction "P$2_P$2") (pintype "passive"))
      (node (ref "U15") (pin "17") (pinfunction "~{RESET}_17") (pintype "input"))
    )
    (net (code "115") (name "PA0") (class "Default")
      (node (ref "XIO") (pin "3") (pinfunction "3_3") (pintype "passive"))
    )
    (net (code "116") (name "PA1") (class "Default")
      (node (ref "XIO") (pin "4") (pinfunction "4_4") (pintype "passive"))
    )
    (net (code "117") (name "PA2") (class "Default")
      (node (ref "XIO") (pin "5") (pinfunction "5_5") (pintype "passive"))
    )
    (net (code "118") (name "PA3") (class "Default")
      (node (ref "XIO") (pin "6") (pinfunction "6_6") (pintype "passive"))
    )
    (net (code "119") (name "PA4") (class "Default")
      (node (ref "XIO") (pin "7") (pinfunction "7_7") (pintype "passive"))
    )
    (net (code "120") (name "PA5") (class "Default")
      (node (ref "XIO") (pin "8") (pinfunction "8_8") (pintype "passive"))
    )
    (net (code "121") (name "PA6") (class "Default")
      (node (ref "XIO") (pin "9") (pinfunction "9_9") (pintype "passive"))
    )
    (net (code "122") (name "PA7") (class "Default")
      (node (ref "XIO") (pin "10") (pinfunction "10_10") (pintype "passive"))
    )
    (net (code "123") (name "PB4") (class "Default")
      (node (ref "JP1") (pin "8") (pinfunction "8_8") (pintype "passive"))
    )
    (net (code "124") (name "PB5") (class "Default")
      (node (ref "JP1") (pin "7") (pinfunction "7_7") (pintype "passive"))
    )
    (net (code "125") (name "PC0") (class "Default")
      (node (ref "XIO") (pin "18") (pinfunction "18_18") (pintype "passive"))
    )
    (net (code "126") (name "PC1") (class "Default")
      (node (ref "XIO") (pin "17") (pinfunction "17_17") (pintype "passive"))
    )
    (net (code "127") (name "PC2") (class "Default")
      (node (ref "XIO") (pin "16") (pinfunction "16_16") (pintype "passive"))
    )
    (net (code "128") (name "PC3") (class "Default")
      (node (ref "XIO") (pin "15") (pinfunction "15_15") (pintype "passive"))
    )
    (net (code "129") (name "PC4") (class "Default")
      (node (ref "XIO") (pin "14") (pinfunction "14_14") (pintype "passive"))
    )
    (net (code "130") (name "PC5") (class "Default")
      (node (ref "XIO") (pin "13") (pinfunction "13_13") (pintype "passive"))
    )
    (net (code "131") (name "PC6") (class "Default")
      (node (ref "XIO") (pin "12") (pinfunction "12_12") (pintype "passive"))
    )
    (net (code "132") (name "PC7") (class "Default")
      (node (ref "XIO") (pin "11") (pinfunction "11_11") (pintype "passive"))
    )
    (net (code "133") (name "PCK1") (class "Default")
      (node (ref "JP1") (pin "5") (pinfunction "5_5") (pintype "passive"))
      (node (ref "Q12") (pin "P$1") (pinfunction "GATE_P$1") (pintype "bidirectional"))
    )
    (net (code "134") (name "PCK2") (class "Default")
      (node (ref "JP1") (pin "6") (pinfunction "6_6") (pintype "passive"))
      (node (ref "Q11") (pin "P$1") (pinfunction "GATE_P$1") (pintype "bidirectional"))
    )
    (net (code "135") (name "PD7") (class "Default")
      (node (ref "XIO") (pin "19") (pinfunction "19_19") (pintype "passive"))
    )
    (net (code "136") (name "PG0") (class "Default")
      (node (ref "XIO") (pin "22") (pinfunction "22_22") (pintype "passive"))
    )
    (net (code "137") (name "PG1") (class "Default")
      (node (ref "XIO") (pin "21") (pinfunction "21_21") (pintype "passive"))
    )
    (net (code "138") (name "PG2") (class "Default")
      (node (ref "XIO") (pin "20") (pinfunction "20_20") (pintype "passive"))
    )
    (net (code "139") (name "PH6") (class "Default")
      (node (ref "JP1") (pin "9") (pinfunction "9_9") (pintype "passive"))
    )
    (net (code "140") (name "PL2") (class "Default")
      (node (ref "XIO") (pin "28") (pinfunction "28_28") (pintype "passive"))
    )
    (net (code "141") (name "PL3") (class "Default")
      (node (ref "XIO") (pin "27") (pinfunction "27_27") (pintype "passive"))
    )
    (net (code "142") (name "PL6") (class "Default")
      (node (ref "XIO") (pin "24") (pinfunction "24_24") (pintype "passive"))
    )
    (net (code "143") (name "PL7") (class "Default")
      (node (ref "XIO") (pin "23") (pinfunction "23_23") (pintype "passive"))
    )
    (net (code "144") (name "PUMP_EN") (class "Default")
      (node (ref "Q9") (pin "P$1") (pinfunction "GATE_P$1") (pintype "bidirectional"))
      (node (ref "XIO") (pin "30") (pinfunction "30_30") (pintype "passive"))
    )
    (net (code "145") (name "PUMP_POWER") (class "Default")
      (node (ref "CON11") (pin "P$1") (pinfunction "P$1_P$1") (pintype "bidirectional"))
      (node (ref "CON11") (pin "P$2") (pinfunction "P$1_P$2") (pintype "bidirectional"))
      (node (ref "RELAY3") (pin "87") (pinfunction "87_87") (pintype "bidirectional"))
    )
    (net (code "146") (name "RELAY_COM_A") (class "Default")
      (node (ref "CON9") (pin "P$2") (pinfunction "P$2_P$2") (pintype "bidirectional"))
      (node (ref "RELAY1") (pin "P$4") (pinfunction "P$4_P$4") (pintype "bidirectional"))
    )
    (net (code "147") (name "RELAY_COM_B") (class "Default")
      (node (ref "CON10") (pin "P$2") (pinfunction "P$2_P$2") (pintype "bidirectional"))
      (node (ref "RELAY1") (pin "P$9") (pinfunction "P$9_P$9") (pintype "bidirectional"))
    )
    (net (code "148") (name "RELAY_EN") (class "Default")
      (node (ref "Q10") (pin "P$1") (pinfunction "G_P$1") (pintype "passive"))
      (node (ref "XIO") (pin "29") (pinfunction "29_29") (pintype "passive"))
    )
    (net (code "149") (name "RELAY_NC_A") (class "Default")
      (node (ref "CON9") (pin "P$1") (pinfunction "P$1_P$1") (pintype "bidirectional"))
      (node (ref "RELAY1") (pin "P$3") (pinfunction "P$3_P$3") (pintype "bidirectional"))
    )
    (net (code "150") (name "RELAY_NC_B") (class "Default")
      (node (ref "CON10") (pin "P$3") (pinfunction "P$3_P$3") (pintype "bidirectional"))
      (node (ref "RELAY1") (pin "P$10") (pinfunction "P$10_P$10") (pintype "bidirectional"))
    )
    (net (code "151") (name "RELAY_NO_A") (class "Default")
      (node (ref "CON9") (pin "P$3") (pinfunction "P$3_P$3") (pintype "bidirectional"))
      (node (ref "RELAY1") (pin "P$5") (pinfunction "P$5_P$5") (pintype "bidirectional"))
    )
    (net (code "152") (name "RELAY_NO_B") (class "Default")
      (node (ref "CON10") (pin "P$1") (pinfunction "P$1_P$1") (pintype "bidirectional"))
      (node (ref "RELAY1") (pin "P$8") (pinfunction "P$8_P$8") (pintype "bidirectional"))
    )
    (net (code "153") (name "RESET") (class "Default")
      (node (ref "POWER") (pin "3") (pinfunction "3_3") (pintype "passive"))
    )
    (net (code "154") (name "RXD1") (class "Default")
      (node (ref "COMMUNICATION") (pin "3") (pinfunction "3_3") (pintype "passive"))
    )
    (net (code "155") (name "RXD2") (class "Default")
      (node (ref "COMMUNICATION") (pin "5") (pinfunction "5_5") (pintype "passive"))
    )
    (net (code "156") (name "RXD3") (class "Default")
      (node (ref "COMMUNICATION") (pin "7") (pinfunction "7_7") (pintype "passive"))
    )
    (net (code "157") (name "RX_CAN") (class "Default")
      (node (ref "D20") (pin "CATHODE") (pinfunction "CATHODE_CATHODE") (pintype "power_in"))
      (node (ref "U14") (pin "4") (pinfunction "RXD_4") (pintype "bidirectional"))
      (node (ref "U15") (pin "2") (pinfunction "RXCAN_2") (pintype "input"))
    )
    (net (code "158") (name "S1_G") (class "Default")
      (node (ref "Q3") (pin "P$4") (pinfunction "GATE_P$4") (pintype "bidirectional"))
      (node (ref "R1") (pin "P$1") (pinfunction "P$1_P$1") (pintype "passive"))
      (node (ref "U1") (pin "5") (pinfunction "OUTB_5") (pintype "bidirectional"))
    )
    (net (code "159") (name "S1_PWM") (class "Default")
      (node (ref "PWML") (pin "6") (pinfunction "6_6") (pintype "passive"))
      (node (ref "U1") (pin "4") (pinfunction "INB_4") (pintype "bidirectional"))
    )
    (net (code "160") (name "S1_SENS_N") (class "Default")
      (node (ref "R11") (pin "P$2") (pinfunction "P$2_P$2") (pintype "passive"))
      (node (ref "R15") (pin "P$2") (pinfunction "P$2_P$2") (pintype "passive"))
      (node (ref "R36") (pin "P$1") (pinfunction "P$1_P$1") (pintype "passive"))
    )
    (net (code "161") (name "S1_SENS_OUT") (class "Default")
      (node (ref "ADCL") (pin "1") (pinfunction "1_1") (pintype "passive"))
      (node (ref "C27") (pin "P$1") (pinfunction "P$1_P$1") (pintype "passive"))
      (node (ref "R33") (pin "P$2") (pinfunction "P$2_P$2") (pintype "passive"))
      (node (ref "R42") (pin "P$2") (pinfunction "P$2_P$2") (pintype "passive"))
    )
    (net (code "162") (name "S1_SENS_P") (class "Default")
      (node (ref "C7") (pin "P$2") (pinfunction "P$2_P$2") (pintype "passive"))
      (node (ref "Q3") (pin "P$1") (pinfunction "SOURCE_P$1") (pintype "bidirectional"))
      (node (ref "Q3") (pin "P$2") (pinfunction "SOURCE_P$2") (pintype "bidirectional"))
      (node (ref "Q3") (pin "P$3") (pinfunction "SOURCE_P$3") (pintype "bidirectional"))
      (node (ref "R11") (pin "P$1") (pinfunction "P$1_P$1") (pintype "passive"))
      (node (ref "R37") (pin "P$1") (pinfunction "P$1_P$1") (pintype "passive"))
    )
    (net (code "163") (name "S2_G") (class "Default")
      (node (ref "Q4") (pin "P$4") (pinfunction "GATE_P$4") (pintype "bidirectional"))
      (node (ref "R2") (pin "P$1") (pinfunction "P$1_P$1") (pintype "passive"))
      (node (ref "U1") (pin "7") (pinfunction "OUTA_7") (pintype "bidirectional"))
    )
    (net (code "164") (name "S2_PWM") (class "Default")
      (node (ref "PWML") (pin "7") (pinfunction "7_7") (pintype "passive"))
      (node (ref "U1") (pin "2") (pinfunction "INA_2") (pintype "bidirectional"))
    )
    (net (code "165") (name "S2_SENS_N") (class "Default")
      (node (ref "R12") (pin "P$2") (pinfunction "P$2_P$2") (pintype "passive"))
      (node (ref "R16") (pin "P$2") (pinfunction "P$2_P$2") (pintype "passive"))
      (node (ref "R38") (pin "P$1") (pinfunction "P$1_P$1") (pintype "passive"))
    )
    (net (code "166") (name "S2_SENS_OUT") (class "Default")
      (node (ref "ADCL") (pin "2") (pinfunction "2_2") (pintype "passive"))
      (node (ref "C30") (pin "P$1") (pinfunction "P$1_P$1") (pintype "passive"))
      (node (ref "R34") (pin "P$2") (pinfunction "P$2_P$2") (pintype "passive"))
      (node (ref "R43") (pin "P$2") (pinfunction "P$2_P$2") (pintype "passive"))
    )
    (net (code "167") (name "S2_SENS_P") (class "Default")
      (node (ref "C8") (pin "P$2") (pinfunction "P$2_P$2") (pintype "passive"))
      (node (ref "Q4") (pin "P$1") (pinfunction "SOURCE_P$1") (pintype "bidirectional"))
      (node (ref "Q4") (pin "P$2") (pinfunction "SOURCE_P$2") (pintype "bidirectional"))
      (node (ref "Q4") (pin "P$3") (pinfunction "SOURCE_P$3") (pintype "bidirectional"))
      (node (ref "R12") (pin "P$1") (pinfunction "P$1_P$1") (pintype "passive"))
      (node (ref "R39") (pin "P$1") (pinfunction "P$1_P$1") (pintype "passive"))
    )
    (net (code "168") (name "S3_G") (class "Default")
      (node (ref "Q1") (pin "P$4") (pinfunction "GATE_P$4") (pintype "bidirectional"))
      (node (ref "R13") (pin "P$1") (pinfunction "P$1_P$1") (pintype "passive"))
      (node (ref "U2") (pin "5") (pinfunction "OUTB_5") (pintype "bidirectional"))
    )
    (net (code "169") (name "S3_PWM") (class "Default")
      (node (ref "PWML") (pin "3") (pinfunction "3_3") (pintype "passive"))
      (node (ref "U2") (pin "4") (pinfunction "INB_4") (pintype "bidirectional"))
    )
    (net (code "170") (name "S3_SENS_N") (class "Default")
      (node (ref "R40") (pin "P$1") (pinfunction "P$1_P$1") (pintype "passive"))
      (node (ref "R7") (pin "P$2") (pinfunction "P$2_P$2") (pintype "passive"))
      (node (ref "R9") (pin "P$2") (pinfunction "P$2_P$2") (pintype "passive"))
    )
    (net (code "171") (name "S3_SENS_OUT") (class "Default")
      (node (ref "ADCL") (pin "3") (pinfunction "3_3") (pintype "passive"))
      (node (ref "C33") (pin "P$1") (pinfunction "P$1_P$1") (pintype "passive"))
      (node (ref "R35") (pin "P$2") (pinfunction "P$2_P$2") (pintype "passive"))
      (node (ref "R44") (pin "P$2") (pinfunction "P$2_P$2") (pintype "passive"))
    )
    (net (code "172") (name "S3_SENS_P") (class "Default")
      (node (ref "C3") (pin "P$2") (pinfunction "P$2_P$2") (pintype "passive"))
      (node (ref "Q1") (pin "P$1") (pinfunction "SOURCE_P$1") (pintype "bidirectional"))
      (node (ref "Q1") (pin "P$2") (pinfunction "SOURCE_P$2") (pintype "bidirectional"))
      (node (ref "Q1") (pin "P$3") (pinfunction "SOURCE_P$3") (pintype "bidirectional"))
      (node (ref "R41") (pin "P$1") (pinfunction "P$1_P$1") (pintype "passive"))
      (node (ref "R7") (pin "P$1") (pinfunction "P$1_P$1") (pintype "passive"))
    )
    (net (code "173") (name "S4_G") (class "Default")
      (node (ref "Q2") (pin "P$4") (pinfunction "GATE_P$4") (pintype "bidirectional"))
      (node (ref "R14") (pin "P$1") (pinfunction "P$1_P$1") (pintype "passive"))
      (node (ref "U2") (pin "7") (pinfunction "OUTA_7") (pintype "bidirectional"))
    )
    (net (code "174") (name "S4_PWM") (class "Default")
      (node (ref "PWML") (pin "4") (pinfunction "4_4") (pintype "passive"))
      (node (ref "U2") (pin "2") (pinfunction "INA_2") (pintype "bidirectional"))
    )
    (net (code "175") (name "S4_SENS_N") (class "Default")
      (node (ref "R10") (pin "P$2") (pinfunction "P$2_P$2") (pintype "passive"))
      (node (ref "R58") (pin "P$1") (pinfunction "P$1_P$1") (pintype "passive"))
      (node (ref "R8") (pin "P$2") (pinfunction "P$2_P$2") (pintype "passive"))
    )
    (net (code "176") (name "S4_SENS_OUT") (class "Default")
      (node (ref "ADCL") (pin "4") (pinfunction "4_4") (pintype "passive"))
      (node (ref "C36") (pin "P$1") (pinfunction "P$1_P$1") (pintype "passive"))
      (node (ref "R57") (pin "P$2") (pinfunction "P$2_P$2") (pintype "passive"))
      (node (ref "R60") (pin "P$2") (pinfunction "P$2_P$2") (pintype "passive"))
    )
    (net (code "177") (name "S4_SENS_P") (class "Default")
      (node (ref "C4") (pin "P$2") (pinfunction "P$2_P$2") (pintype "passive"))
      (node (ref "Q2") (pin "P$1") (pinfunction "SOURCE_P$1") (pintype "bidirectional"))
      (node (ref "Q2") (pin "P$2") (pinfunction "SOURCE_P$2") (pintype "bidirectional"))
      (node (ref "Q2") (pin "P$3") (pinfunction "SOURCE_P$3") (pintype "bidirectional"))
      (node (ref "R59") (pin "P$1") (pinfunction "P$1_P$1") (pintype "passive"))
      (node (ref "R8") (pin "P$1") (pinfunction "P$1_P$1") (pintype "passive"))
    )
    (net (code "178") (name "S5_G") (class "Default")
      (node (ref "Q5") (pin "P$4") (pinfunction "GATE_P$4") (pintype "bidirectional"))
      (node (ref "R17") (pin "P$1") (pinfunction "P$1_P$1") (pintype "passive"))
      (node (ref "U3") (pin "7") (pinfunction "OUTA_7") (pintype "bidirectional"))
    )
    (net (code "179") (name "S5_PWM") (class "Default")
      (node (ref "PWML") (pin "8") (pinfunction "8_8") (pintype "passive"))
      (node (ref "U3") (pin "2") (pinfunction "INA_2") (pintype "bidirectional"))
    )
    (net (code "180") (name "S5_SENS_N") (class "Default")
      (node (ref "R25") (pin "P$2") (pinfunction "P$2_P$2") (pintype "passive"))
      (node (ref "R29") (pin "P$2") (pinfunction "P$2_P$2") (pintype "passive"))
      (node (ref "R68") (pin "P$1") (pinfunction "P$1_P$1") (pintype "passive"))
    )
    (net (code "181") (name "S5_SENS_OUT") (class "Default")
      (node (ref "ADCL") (pin "5") (pinfunction "5_5") (pintype "passive"))
      (node (ref "C39") (pin "P$1") (pinfunction "P$1_P$1") (pintype "passive"))
      (node (ref "R65") (pin "P$2") (pinfunction "P$2_P$2") (pintype "passive"))
      (node (ref "R74") (pin "P$2") (pinfunction "P$2_P$2") (pintype "passive"))
    )
    (net (code "182") (name "S5_SENS_P") (class "Default")
      (node (ref "C19") (pin "P$2") (pinfunction "P$2_P$2") (pintype "passive"))
      (node (ref "Q5") (pin "P$1") (pinfunction "SOURCE_P$1") (pintype "bidirectional"))
      (node (ref "Q5") (pin "P$2") (pinfunction "SOURCE_P$2") (pintype "bidirectional"))
      (node (ref "Q5") (pin "P$3") (pinfunction "SOURCE_P$3") (pintype "bidirectional"))
      (node (ref "R25") (pin "P$1") (pinfunction "P$1_P$1") (pintype "passive"))
      (node (ref "R69") (pin "P$1") (pinfunction "P$1_P$1") (pintype "passive"))
    )
    (net (code "183") (name "S6_G") (class "Default")
      (node (ref "Q6") (pin "P$4") (pinfunction "GATE_P$4") (pintype "bidirectional"))
      (node (ref "R18") (pin "P$1") (pinfunction "P$1_P$1") (pintype "passive"))
      (node (ref "U3") (pin "5") (pinfunction "OUTB_5") (pintype "bidirectional"))
    )
    (net (code "184") (name "S6_PWM") (class "Default")
      (node (ref "JP1") (pin "10") (pinfunction "10_10") (pintype "passive"))
      (node (ref "U3") (pin "4") (pinfunction "INB_4") (pintype "bidirectional"))
    )
    (net (code "185") (name "S6_SENS_N") (class "Default")
      (node (ref "R26") (pin "P$2") (pinfunction "P$2_P$2") (pintype "passive"))
      (node (ref "R30") (pin "P$2") (pinfunction "P$2_P$2") (pintype "passive"))
      (node (ref "R70") (pin "P$1") (pinfunction "P$1_P$1") (pintype "passive"))
    )
    (net (code "186") (name "S6_SENS_OUT") (class "Default")
      (node (ref "ADCL") (pin "6") (pinfunction "6_6") (pintype "passive"))
      (node (ref "C42") (pin "P$1") (pinfunction "P$1_P$1") (pintype "passive"))
      (node (ref "R66") (pin "P$2") (pinfunction "P$2_P$2") (pintype "passive"))
      (node (ref "R75") (pin "P$2") (pinfunction "P$2_P$2") (pintype "passive"))
    )
    (net (code "187") (name "S6_SENS_P") (class "Default")
      (node (ref "C20") (pin "P$2") (pinfunction "P$2_P$2") (pintype "passive"))
      (node (ref "Q6") (pin "P$1") (pinfunction "SOURCE_P$1") (pintype "bidirectional"))
      (node (ref "Q6") (pin "P$2") (pinfunction "SOURCE_P$2") (pintype "bidirectional"))
      (node (ref "Q6") (pin "P$3") (pinfunction "SOURCE_P$3") (pintype "bidirectional"))
      (node (ref "R26") (pin "P$1") (pinfunction "P$1_P$1") (pintype "passive"))
      (node (ref "R71") (pin "P$1") (pinfunction "P$1_P$1") (pintype "passive"))
    )
    (net (code "188") (name "S7_G") (class "Default")
      (node (ref "Q7") (pin "P$4") (pinfunction "GATE_P$4") (pintype "bidirectional"))
      (node (ref "R19") (pin "P$1") (pinfunction "P$1_P$1") (pintype "passive"))
      (node (ref "U4") (pin "7") (pinfunction "OUTA_7") (pintype "bidirectional"))
    )
    (net (code "189") (name "S7_PWM") (class "Default")
      (node (ref "U4") (pin "2") (pinfunction "INA_2") (pintype "bidirectional"))
      (node (ref "XIO") (pin "25") (pinfunction "25_25") (pintype "passive"))
    )
    (net (code "190") (name "S7_SENS_N") (class "Default")
      (node (ref "R27") (pin "P$2") (pinfunction "P$2_P$2") (pintype "passive"))
      (node (ref "R31") (pin "P$2") (pinfunction "P$2_P$2") (pintype "passive"))
      (node (ref "R72") (pin "P$1") (pinfunction "P$1_P$1") (pintype "passive"))
    )
    (net (code "191") (name "S7_SENS_OUT") (class "Default")
      (node (ref "ADCL") (pin "7") (pinfunction "7_7") (pintype "passive"))
      (node (ref "C45") (pin "P$1") (pinfunction "P$1_P$1") (pintype "passive"))
      (node (ref "R67") (pin "P$2") (pinfunction "P$2_P$2") (pintype "passive"))
      (node (ref "R76") (pin "P$2") (pinfunction "P$2_P$2") (pintype "passive"))
    )
    (net (code "192") (name "S7_SENS_P") (class "Default")
      (node (ref "C21") (pin "P$2") (pinfunction "P$2_P$2") (pintype "passive"))
      (node (ref "Q7") (pin "P$1") (pinfunction "SOURCE_P$1") (pintype "bidirectional"))
      (node (ref "Q7") (pin "P$2") (pinfunction "SOURCE_P$2") (pintype "bidirectional"))
      (node (ref "Q7") (pin "P$3") (pinfunction "SOURCE_P$3") (pintype "bidirectional"))
      (node (ref "R27") (pin "P$1") (pinfunction "P$1_P$1") (pintype "passive"))
      (node (ref "R73") (pin "P$1") (pinfunction "P$1_P$1") (pintype "passive"))
    )
    (net (code "193") (name "S8_G") (class "Default")
      (node (ref "Q8") (pin "P$4") (pinfunction "GATE_P$4") (pintype "bidirectional"))
      (node (ref "R20") (pin "P$1") (pinfunction "P$1_P$1") (pintype "passive"))
      (node (ref "U4") (pin "5") (pinfunction "OUTB_5") (pintype "bidirectional"))
    )
    (net (code "194") (name "S8_PWM") (class "Default")
      (node (ref "U4") (pin "4") (pinfunction "INB_4") (pintype "bidirectional"))
      (node (ref "XIO") (pin "26") (pinfunction "26_26") (pintype "passive"))
    )
    (net (code "195") (name "S8_SENS_N") (class "Default")
      (node (ref "R28") (pin "P$2") (pinfunction "P$2_P$2") (pintype "passive"))
      (node (ref "R32") (pin "P$2") (pinfunction "P$2_P$2") (pintype "passive"))
      (node (ref "R90") (pin "P$1") (pinfunction "P$1_P$1") (pintype "passive"))
    )
    (net (code "196") (name "S8_SENS_OUT") (class "Default")
      (node (ref "ADCL") (pin "8") (pinfunction "8_8") (pintype "passive"))
      (node (ref "C48") (pin "P$1") (pinfunction "P$1_P$1") (pintype "passive"))
      (node (ref "R89") (pin "P$2") (pinfunction "P$2_P$2") (pintype "passive"))
      (node (ref "R92") (pin "P$2") (pinfunction "P$2_P$2") (pintype "passive"))
    )
    (net (code "197") (name "S8_SENS_P") (class "Default")
      (node (ref "C22") (pin "P$2") (pinfunction "P$2_P$2") (pintype "passive"))
      (node (ref "Q8") (pin "P$1") (pinfunction "SOURCE_P$1") (pintype "bidirectional"))
      (node (ref "Q8") (pin "P$2") (pinfunction "SOURCE_P$2") (pintype "bidirectional"))
      (node (ref "Q8") (pin "P$3") (pinfunction "SOURCE_P$3") (pintype "bidirectional"))
      (node (ref "R28") (pin "P$1") (pinfunction "P$1_P$1") (pintype "passive"))
      (node (ref "R91") (pin "P$1") (pinfunction "P$1_P$1") (pintype "passive"))
    )
    (net (code "198") (name "SCK") (class "Default")
      (node (ref "U15") (pin "13") (pinfunction "SCK_13") (pintype "input"))
      (node (ref "XIO") (pin "33") (pinfunction "33_33") (pintype "passive"))
    )
    (net (code "199") (name "SCL") (class "Default")
      (node (ref "JP1") (pin "1") (pinfunction "1_1") (pintype "passive"))
    )
    (net (code "200") (name "SDA") (class "Default")
      (node (ref "JP1") (pin "2") (pinfunction "2_2") (pintype "passive"))
    )
    (net (code "201") (name "TXD1") (class "Default")
      (node (ref "COMMUNICATION") (pin "4") (pinfunction "4_4") (pintype "passive"))
    )
    (net (code "202") (name "TXD2") (class "Default")
      (node (ref "COMMUNICATION") (pin "6") (pinfunction "6_6") (pintype "passive"))
    )
    (net (code "203") (name "TXD3") (class "Default")
      (node (ref "COMMUNICATION") (pin "8") (pinfunction "8_8") (pintype "passive"))
    )
    (net (code "204") (name "TX_CAN") (class "Default")
      (node (ref "D19") (pin "CATHODE") (pinfunction "CATHODE_CATHODE") (pintype "power_in"))
      (node (ref "U14") (pin "1") (pinfunction "TXD_1") (pintype "bidirectional"))
      (node (ref "U15") (pin "1") (pinfunction "TXCAN_1") (pintype "output"))
    )
    (net (code "205") (name "V+") (class "Default")
      (node (ref "CON16") (pin "P$2") (pinfunction "P$2_P$2") (pintype "bidirectional"))
      (node (ref "F1") (pin "P$1") (pinfunction "P$1_P$1") (pintype "bidirectional"))
      (node (ref "F1") (pin "P$2") (pinfunction "P$1_P$2") (pintype "bidirectional"))
      (node (ref "F1") (pin "P$3") (pinfunction "P$1_P$3") (pintype "bidirectional"))
      (node (ref "F1") (pin "P$4") (pinfunction "P$1_P$4") (pintype "bidirectional"))
      (node (ref "RELAY3") (pin "86") (pinfunction "86_86") (pintype "bidirectional"))
      (node (ref "U13") (pin "P$1") (pinfunction "VIN_P$1") (pintype "bidirectional"))
    )
    (net (code "206") (name "VB1") (class "Default")
      (node (ref "C11") (pin "P$1") (pinfunction "P$1_P$1") (pintype "passive"))
      (node (ref "C12") (pin "P$1") (pinfunction "P$1_P$1") (pintype "passive"))
      (node (ref "C17") (pin "P$1") (pinfunction "P$1_P$1") (pintype "passive"))
      (node (ref "C18") (pin "P$1") (pinfunction "P$1_P$1") (pintype "passive"))
      (node (ref "C23") (pin "P$1") (pinfunction "P$1_P$1") (pintype "passive"))
      (node (ref "C24") (pin "P$1") (pinfunction "P$1_P$1") (pintype "passive"))
      (node (ref "C5") (pin "P$1") (pinfunction "P$1_P$1") (pintype "passive"))
      (node (ref "C6") (pin "P$1") (pinfunction "P$1_P$1") (pintype "passive"))
      (node (ref "F1") (pin "P$5") (pinfunction "P$2_P$5") (pintype "bidirectional"))
      (node (ref "F1") (pin "P$6") (pinfunction "P$2_P$6") (pintype "bidirectional"))
      (node (ref "F1") (pin "P$7") (pinfunction "P$2_P$7") (pintype "bidirectional"))
      (node (ref "F1") (pin "P$8") (pinfunction "P$2_P$8") (pintype "bidirectional"))
      (node (ref "L1") (pin "P$1") (pinfunction "P$1_P$1") (pintype "passive"))
      (node (ref "L2") (pin "P$1") (pinfunction "P$1_P$1") (pintype "passive"))
      (node (ref "L3") (pin "P$1") (pinfunction "P$1_P$1") (pintype "passive"))
      (node (ref "L4") (pin "P$1") (pinfunction "P$1_P$1") (pintype "passive"))
      (node (ref "L5") (pin "P$1") (pinfunction "P$1_P$1") (pintype "passive"))
      (node (ref "L6") (pin "P$1") (pinfunction "P$1_P$1") (pintype "passive"))
      (node (ref "L7") (pin "P$1") (pinfunction "P$1_P$1") (pintype "passive"))
      (node (ref "L8") (pin "P$1") (pinfunction "P$1_P$1") (pintype "passive"))
      (node (ref "R120") (pin "P$1") (pinfunction "P$1_P$1") (pintype "passive"))
      (node (ref "U1") (pin "1") (pinfunction "ENA_1") (pintype "bidirectional"))
      (node (ref "U1") (pin "6") (pinfunction "VDD_6") (pintype "bidirectional"))
      (node (ref "U1") (pin "8") (pinfunction "ENB_8") (pintype "bidirectional"))
      (node (ref "U2") (pin "1") (pinfunction "ENA_1") (pintype "bidirectional"))
      (node (ref "U2") (pin "6") (pinfunction "VDD_6") (pintype "bidirectional"))
      (node (ref "U2") (pin "8") (pinfunction "ENB_8") (pintype "bidirectional"))
      (node (ref "U3") (pin "1") (pinfunction "ENA_1") (pintype "bidirectional"))
      (node (ref "U3") (pin "6") (pinfunction "VDD_6") (pintype "bidirectional"))
      (node (ref "U3") (pin "8") (pinfunction "ENB_8") (pintype "bidirectional"))
      (node (ref "U4") (pin "1") (pinfunction "ENA_1") (pintype "bidirectional"))
      (node (ref "U4") (pin "6") (pinfunction "VDD_6") (pintype "bidirectional"))
      (node (ref "U4") (pin "8") (pinfunction "ENB_8") (pintype "bidirectional"))
    )
    (net (code "207") (name "VIN") (class "Default")
      (node (ref "POWER") (pin "8") (pinfunction "8_8") (pintype "passive"))
    )
    (net (code "208") (name "VPUMP") (class "Default")
      (node (ref "CON17") (pin "P$3") (pinfunction "P$2_P$3") (pintype "bidirectional"))
      (node (ref "CON17") (pin "P$4") (pinfunction "P$2_P$4") (pintype "bidirectional"))
      (node (ref "F3") (pin "P$5") (pinfunction "P$2_P$5") (pintype "bidirectional"))
      (node (ref "F3") (pin "P$6") (pinfunction "P$2_P$6") (pintype "bidirectional"))
      (node (ref "F3") (pin "P$7") (pinfunction "P$2_P$7") (pintype "bidirectional"))
      (node (ref "F3") (pin "P$8") (pinfunction "P$2_P$8") (pintype "bidirectional"))
    )
    (net (code "209") (name "unconnected-(COMMUNICATION-Pad2)") (class "Default")
      (node (ref "COMMUNICATION") (pin "2") (pinfunction "2_2") (pintype "passive"))
    )
    (net (code "210") (name "unconnected-(POWER-Pad1)") (class "Default")
      (node (ref "POWER") (pin "1") (pinfunction "1_1") (pintype "passive"))
    )
    (net (code "211") (name "unconnected-(PWML-Pad1)") (class "Default")
      (node (ref "PWML") (pin "1") (pinfunction "1_1") (pintype "passive"))
    )
    (net (code "212") (name "unconnected-(PWML-Pad2)") (class "Default")
      (node (ref "PWML") (pin "2") (pinfunction "2_2") (pintype "passive"))
    )
    (net (code "213") (name "unconnected-(PWML-Pad5)") (class "Default")
      (node (ref "PWML") (pin "5") (pinfunction "5_5") (pintype "passive"))
    )
    (net (code "214") (name "unconnected-(RELAY3-Pad87A)") (class "Default")
      (node (ref "RELAY3") (pin "87A") (pinfunction "87A_87A") (pintype "bidirectional"))
    )
    (net (code "215") (name "unconnected-(TP1-PadT)") (class "Default")
      (node (ref "TP1") (pin "T") (pinfunction "T_T") (pintype "bidirectional"))
    )
    (net (code "216") (name "unconnected-(TP2-PadT)") (class "Default")
      (node (ref "TP2") (pin "T") (pinfunction "T_T") (pintype "bidirectional"))
    )
    (net (code "217") (name "unconnected-(TP3-PadT)") (class "Default")
      (node (ref "TP3") (pin "T") (pinfunction "T_T") (pintype "bidirectional"))
    )
    (net (code "218") (name "unconnected-(U14-VREF-Pad5)") (class "Default")
      (node (ref "U14") (pin "5") (pinfunction "VREF_5") (pintype "bidirectional"))
    )
    (net (code "219") (name "unconnected-(U15-CLKOUT{slash}SOF-Pad3)") (class "Default")
      (node (ref "U15") (pin "3") (pinfunction "CLKOUT/SOF_3") (pintype "output"))
    )
    (net (code "220") (name "unconnected-(U15-~{RX0BF}-Pad11)") (class "Default")
      (node (ref "U15") (pin "11") (pinfunction "~{RX0BF}_11") (pintype "output"))
    )
    (net (code "221") (name "unconnected-(U15-~{RX1BF}-Pad10)") (class "Default")
      (node (ref "U15") (pin "10") (pinfunction "~{RX1BF}_10") (pintype "output"))
    )
    (net (code "222") (name "unconnected-(U15-~{TX0RTS}-Pad4)") (class "Default")
      (node (ref "U15") (pin "4") (pinfunction "~{TX0RTS}_4") (pintype "input"))
    )
    (net (code "223") (name "unconnected-(U15-~{TX1RTS}-Pad5)") (class "Default")
      (node (ref "U15") (pin "5") (pinfunction "~{TX1RTS}_5") (pintype "input"))
    )
    (net (code "224") (name "unconnected-(U15-~{TX2RTS}-Pad6)") (class "Default")
      (node (ref "U15") (pin "6") (pinfunction "~{TX2RTS}_6") (pintype "input"))
    )
    (net (code "225") (name "unconnected-(XIO-Pad1)") (class "Default")
      (node (ref "XIO") (pin "1") (pinfunction "1_1") (pintype "passive"))
    )
    (net (code "226") (name "unconnected-(XIO-Pad2)") (class "Default")
      (node (ref "XIO") (pin "2") (pinfunction "2_2") (pintype "passive"))
    )
  )
)
